# CM5_Adapter.net
KiCad netlist of a schematic drawn in Altium Designer
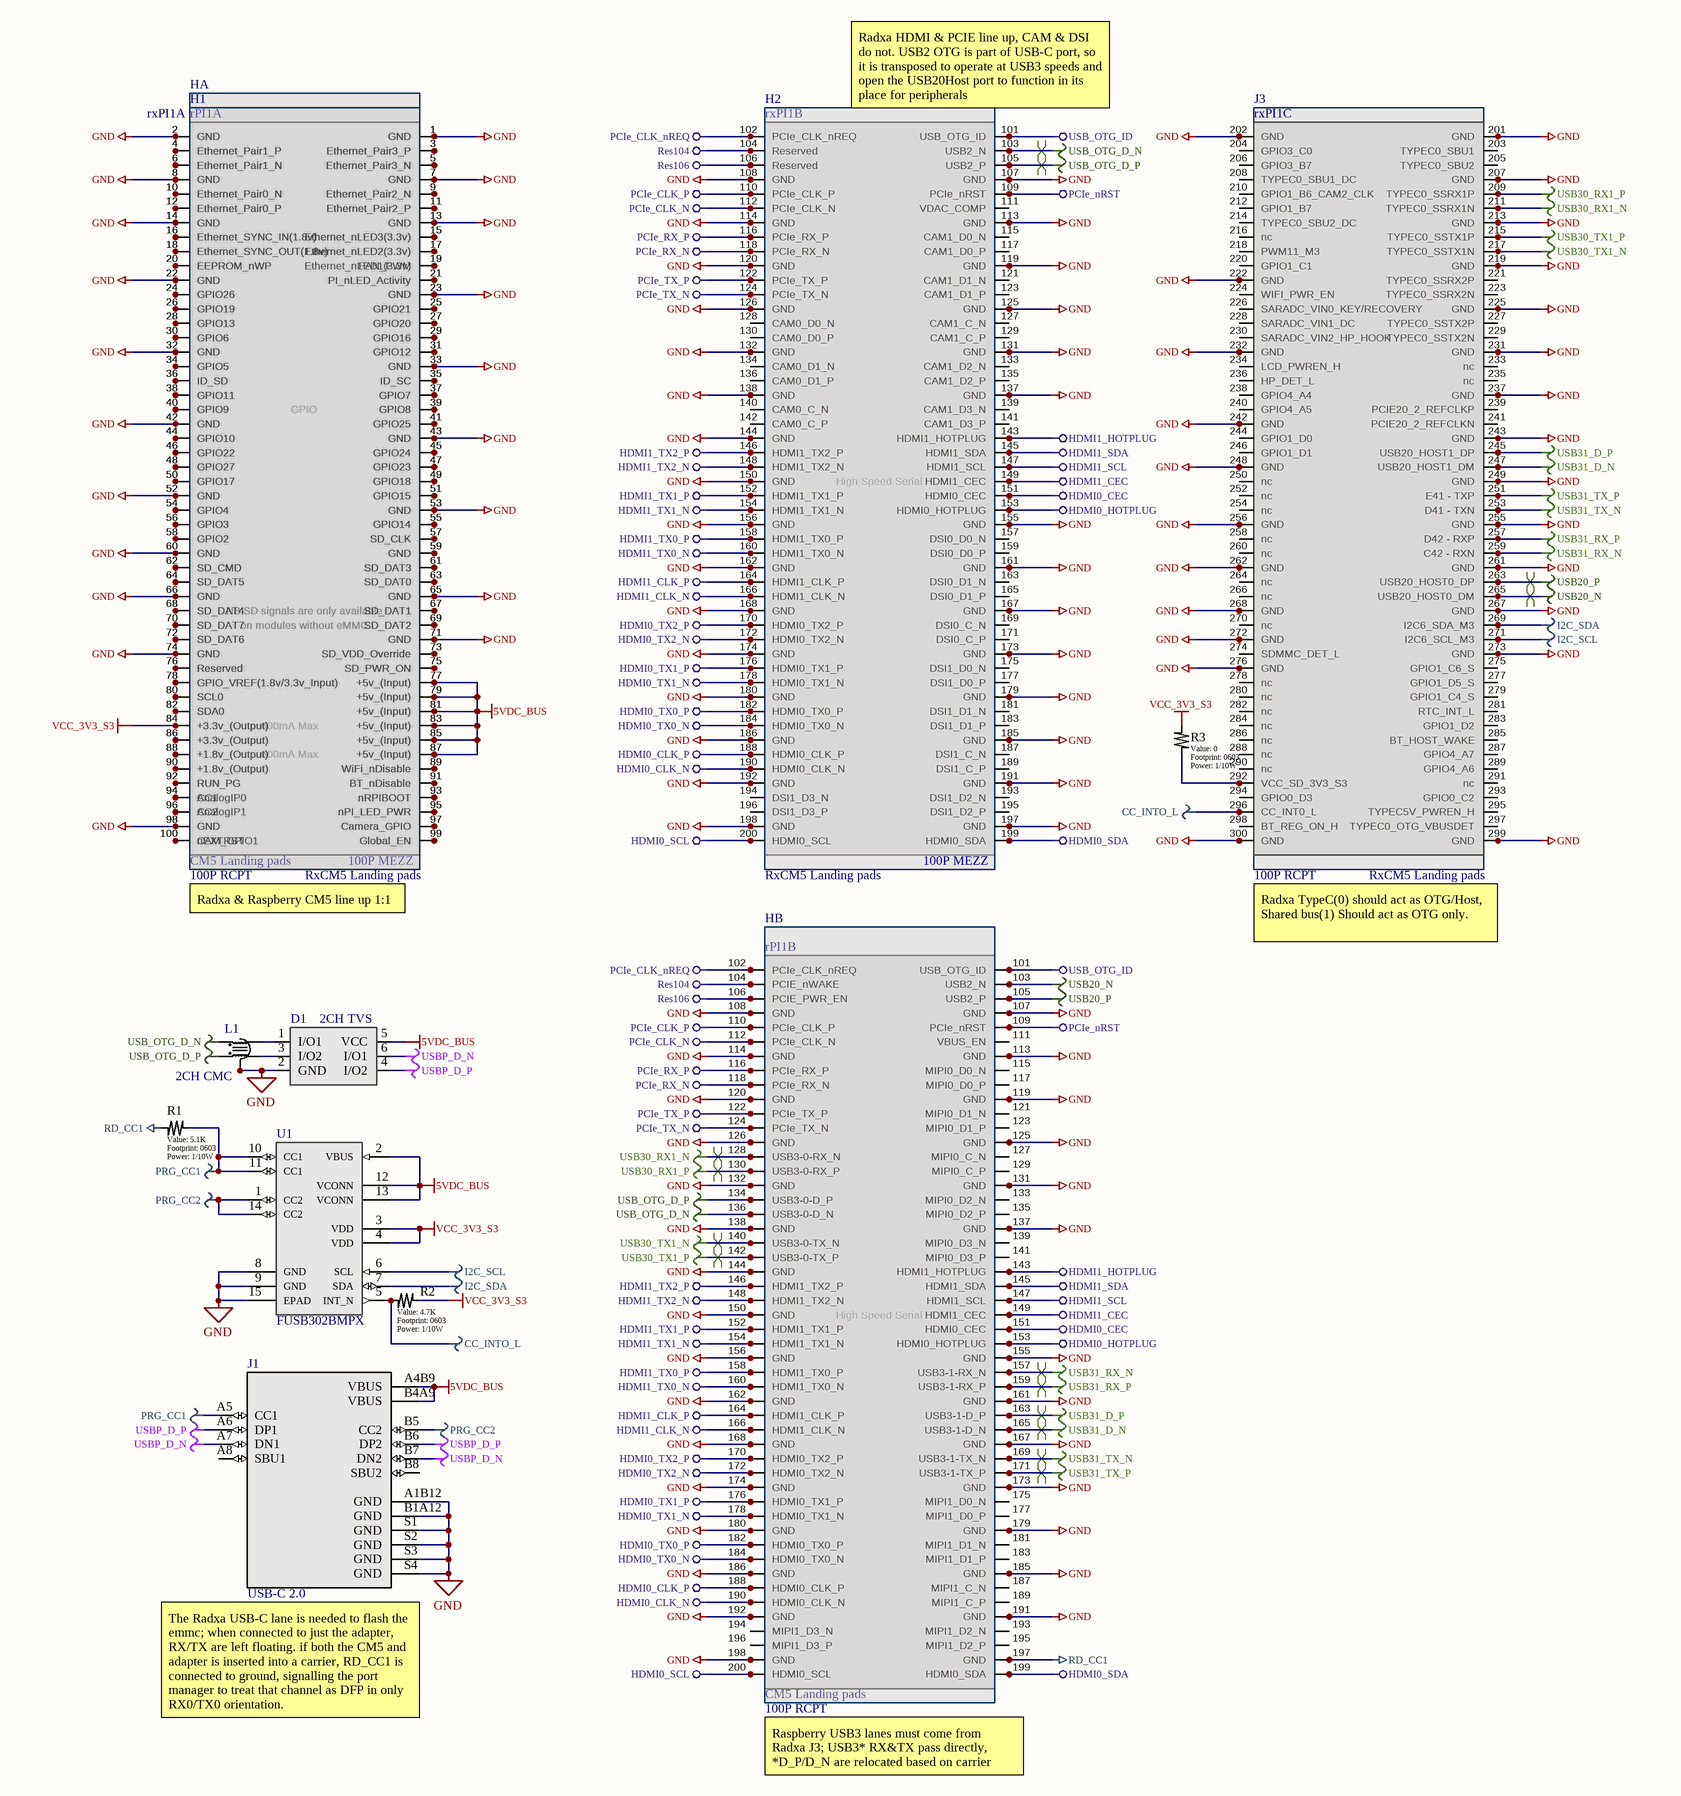
[diagram p0: CM5 Adapter.SchDoc]

(export (version "E")
  (design (tool "Eeschema 10.0.6"))
  (components
    (comp (ref "D1")
      (value "2CH TVS")
      (footprint "FP-SOT886-MFG")
      (description "TVS DIODE 5.5V 6XSON SOT886")
      (fields
        (field (name "OCTOPART") "https://octopart.com/prtr5v0u2f%2C115-nexperia-78741690")
        (field (name "MANUFACTURER") "Nexperia")
      )
      (libsource (lib "Diodes") (part "PRTR5V0U2F,115"))
    )
    (comp (ref "H1")
      (value "100P RCPT")
      (footprint "DF40C-100DS-0.4V(51)")
      (description "100 Position Connector Receptacle, Center Strip Contacts Surface Mount Gold")
      (fields (field (name "MF") "Hirose") (field (name "MP") "DF40C-100DS-0.4V(51)"))
      (libsource (lib "") (part "DF40-100DS RCPT_1_1"))
    )
    (comp (ref "H2")
      (value "100P MEZZ")
      (footprint "DF40C-100DS-0.4V(51)")
      (description "100 Position Connector Receptacle, Center Strip Contacts Surface Mount Gold")
      (fields (field (name "MF") "Hirose") (field (name "MP") "DF40C-100DS-0.4V(51)"))
      (libsource (lib "") (part "DF40-100DS RCPT_1_1"))
    )
    (comp (ref "HA")
      (value "100P MEZZ")
      (footprint "DF40C-100DP-0.4V(51)")
      (description "100 Position Connector Receptacle, Center Strip Contacts Surface Mount Gold")
      (fields (field (name "MF") "Hirose") (field (name "MP") "DF40C-100DS-0.4V(51)"))
      (libsource (lib "SOC_Carrier") (part "DF40-XX-100DS RCPT"))
    )
    (comp (ref "HB")
      (value "100P RCPT")
      (footprint "DF40C-100DP-0.4V(51)")
      (description "100 Position Connector Receptacle, Center Strip Contacts Surface Mount Gold")
      (fields (field (name "MF") "Hirose") (field (name "MP") "DF40C-100DS-0.4V(51)"))
      (libsource (lib "SOC_Carrier") (part "DF40-XX-100DS RCPT"))
    )
    (comp (ref "J1")
      (value "USB-C 2.0")
      (footprint "GT-USB-7010ASV")
      (libsource (lib "Connectors") (part "12402012E212A"))
    )
    (comp (ref "J3")
      (value "100P RCPT")
      (footprint "DF40C-100DS-0.4V(51)")
      (description "100 Position Connector Receptacle, Center Strip Contacts Surface Mount Gold")
      (fields (field (name "MF") "Hirose") (field (name "MP") "DF40C-100DS-0.4V(51)"))
      (libsource (lib "Connectors") (part "DF40-100DS RCPT_1"))
    )
    (comp (ref "L1")
      (value "2CH CMC")
      (footprint "SMD-6-2CH")
      (description "35Ω@100MHz -40℃~+85℃ 4Ω 5V 2 100mA SMD Common Mode Filters ROHS")
      (libsource (lib "Inductors") (part "ICMEF112P350MFR"))
    )
    (comp (ref "R1")
      (value "5.1K")
      (footprint "0603")
      (fields
        (field (name "TOLERANCE") "1%")
        (field (name "POWER") "1/10W")
        (field (name "Comment") "Generic Resistor")
      )
      (libsource (lib "Resistors") (part "Generic Resistor"))
    )
    (comp (ref "R2")
      (value "4.7K")
      (footprint "0603")
      (fields
        (field (name "TOLERANCE") "1%")
        (field (name "POWER") "1/10W")
        (field (name "Comment") "Generic Resistor")
      )
      (libsource (lib "Resistors") (part "Generic Resistor"))
    )
    (comp (ref "R3")
      (value "0")
      (footprint "0603")
      (fields
        (field (name "TOLERANCE") "1%")
        (field (name "POWER") "1/10W")
        (field (name "Comment") "Generic Resistor")
      )
      (libsource (lib "Resistors") (part "Generic Resistor"))
    )
    (comp (ref "rPI1")
      (value "CM5 Landing pads")
      (footprint "rP-200P-CM-REP (top)")
      (libsource (lib "SOC_Carrier") (part "RP-CM5-Rep"))
    )
    (comp (ref "rxPI1")
      (value "RxCM5 Landing pads")
      (footprint "RX-300P-CM-FTPD")
      (libsource (lib "SOC_Carrier") (part "RX-CM5"))
    )
    (comp (ref "U1")
      (value "FUSB302BMPX")
      (footprint "MLP14_2P5X2P5_ONS-L")
      (description "IC USB TYPE C CTLR PROGR 14-MLP")
      (fields (field (name "COPYRIGHT") "Copyright (C) 2025 Ultra Librarian. All rights reserved."))
      (libsource (lib "Misc ICs") (part "FUSB302BMPX"))
    )
  )
  (nets
    (net (code "1") (name "5VDC_BUS") (class "Default")
      (node (ref "D1") (pin "5") (pinfunction "VCC_5") (pintype "power_in"))
      (node (ref "H1") (pin "77") (pinfunction "77_77") (pintype "passive"))
      (node (ref "H1") (pin "79") (pinfunction "79_79") (pintype "passive"))
      (node (ref "H1") (pin "81") (pinfunction "81_81") (pintype "passive"))
      (node (ref "H1") (pin "83") (pinfunction "83_83") (pintype "passive"))
      (node (ref "H1") (pin "85") (pinfunction "85_85") (pintype "passive"))
      (node (ref "H1") (pin "87") (pinfunction "87_87") (pintype "passive"))
      (node (ref "HA") (pin "78") (pinfunction "78_78") (pintype "passive"))
      (node (ref "HA") (pin "80") (pinfunction "80_80") (pintype "passive"))
      (node (ref "HA") (pin "82") (pinfunction "82_82") (pintype "passive"))
      (node (ref "HA") (pin "84") (pinfunction "84_84") (pintype "passive"))
      (node (ref "HA") (pin "86") (pinfunction "86_86") (pintype "passive"))
      (node (ref "HA") (pin "88") (pinfunction "88_88") (pintype "passive"))
      (node (ref "J1") (pin "A4B9") (pinfunction "VBUS_A4B9") (pintype "power_in"))
      (node (ref "J1") (pin "B4A9") (pinfunction "VBUS_B4A9") (pintype "power_in"))
      (node (ref "U1") (pin "12") (pinfunction "VCONN_12") (pintype "power_in"))
      (node (ref "U1") (pin "13") (pinfunction "VCONN_13") (pintype "power_in"))
      (node (ref "U1") (pin "2") (pinfunction "VBUS_2") (pintype "input"))
      (node (ref "rPI1") (pin "77") (pinfunction "+5v_(Input)_77") (pintype "passive"))
      (node (ref "rPI1") (pin "79") (pinfunction "+5v_(Input)_79") (pintype "passive"))
      (node (ref "rPI1") (pin "81") (pinfunction "+5v_(Input)_81") (pintype "passive"))
      (node (ref "rPI1") (pin "83") (pinfunction "+5v_(Input)_83") (pintype "passive"))
      (node (ref "rPI1") (pin "85") (pinfunction "+5v_(Input)_85") (pintype "passive"))
      (node (ref "rPI1") (pin "87") (pinfunction "+5v_(Input)_87") (pintype "passive"))
      (node (ref "rxPI1") (pin "77") (pinfunction "+5v_(Input)_77") (pintype "passive"))
      (node (ref "rxPI1") (pin "79") (pinfunction "+5v_(Input)_79") (pintype "passive"))
      (node (ref "rxPI1") (pin "81") (pinfunction "+5v_(Input)_81") (pintype "passive"))
      (node (ref "rxPI1") (pin "83") (pinfunction "+5v_(Input)_83") (pintype "passive"))
      (node (ref "rxPI1") (pin "85") (pinfunction "+5v_(Input)_85") (pintype "passive"))
      (node (ref "rxPI1") (pin "87") (pinfunction "+5v_(Input)_87") (pintype "passive"))
    )
    (net (code "2") (name "CC_INTO_L") (class "Default")
      (node (ref "J3") (pin "95") (pinfunction "95_95") (pintype "passive"))
      (node (ref "R2") (pin "1") (pinfunction "1_1") (pintype "passive"))
      (node (ref "U1") (pin "5") (pinfunction "INT_N_5") (pintype "output"))
      (node (ref "rxPI1") (pin "296") (pinfunction "CC_INT0_L_296") (pintype "passive"))
    )
    (net (code "3") (name "GND") (class "Default")
      (node (ref "D1") (pin "2") (pinfunction "GND_2") (pintype "power_in"))
      (node (ref "H1") (pin "1") (pinfunction "1_1") (pintype "passive"))
      (node (ref "H1") (pin "13") (pinfunction "13_13") (pintype "passive"))
      (node (ref "H1") (pin "14") (pinfunction "14_14") (pintype "passive"))
      (node (ref "H1") (pin "2") (pinfunction "2_2") (pintype "passive"))
      (node (ref "H1") (pin "22") (pinfunction "22_22") (pintype "passive"))
      (node (ref "H1") (pin "23") (pinfunction "23_23") (pintype "passive"))
      (node (ref "H1") (pin "32") (pinfunction "32_32") (pintype "passive"))
      (node (ref "H1") (pin "33") (pinfunction "33_33") (pintype "passive"))
      (node (ref "H1") (pin "42") (pinfunction "42_42") (pintype "passive"))
      (node (ref "H1") (pin "43") (pinfunction "43_43") (pintype "passive"))
      (node (ref "H1") (pin "52") (pinfunction "52_52") (pintype "passive"))
      (node (ref "H1") (pin "53") (pinfunction "53_53") (pintype "passive"))
      (node (ref "H1") (pin "60") (pinfunction "60_60") (pintype "passive"))
      (node (ref "H1") (pin "65") (pinfunction "65_65") (pintype "passive"))
      (node (ref "H1") (pin "66") (pinfunction "66_66") (pintype "passive"))
      (node (ref "H1") (pin "7") (pinfunction "7_7") (pintype "passive"))
      (node (ref "H1") (pin "71") (pinfunction "71_71") (pintype "passive"))
      (node (ref "H1") (pin "74") (pinfunction "74_74") (pintype "passive"))
      (node (ref "H1") (pin "8") (pinfunction "8_8") (pintype "passive"))
      (node (ref "H1") (pin "98") (pinfunction "98_98") (pintype "passive"))
      (node (ref "H2") (pin "13") (pinfunction "13_13") (pintype "passive"))
      (node (ref "H2") (pin "14") (pinfunction "14_14") (pintype "passive"))
      (node (ref "H2") (pin "19") (pinfunction "19_19") (pintype "passive"))
      (node (ref "H2") (pin "20") (pinfunction "20_20") (pintype "passive"))
      (node (ref "H2") (pin "25") (pinfunction "25_25") (pintype "passive"))
      (node (ref "H2") (pin "26") (pinfunction "26_26") (pintype "passive"))
      (node (ref "H2") (pin "31") (pinfunction "31_31") (pintype "passive"))
      (node (ref "H2") (pin "32") (pinfunction "32_32") (pintype "passive"))
      (node (ref "H2") (pin "37") (pinfunction "37_37") (pintype "passive"))
      (node (ref "H2") (pin "38") (pinfunction "38_38") (pintype "passive"))
      (node (ref "H2") (pin "44") (pinfunction "44_44") (pintype "passive"))
      (node (ref "H2") (pin "50") (pinfunction "50_50") (pintype "passive"))
      (node (ref "H2") (pin "55") (pinfunction "55_55") (pintype "passive"))
      (node (ref "H2") (pin "56") (pinfunction "56_56") (pintype "passive"))
      (node (ref "H2") (pin "61") (pinfunction "61_61") (pintype "passive"))
      (node (ref "H2") (pin "62") (pinfunction "62_62") (pintype "passive"))
      (node (ref "H2") (pin "67") (pinfunction "67_67") (pintype "passive"))
      (node (ref "H2") (pin "68") (pinfunction "68_68") (pintype "passive"))
      (node (ref "H2") (pin "7") (pinfunction "7_7") (pintype "passive"))
      (node (ref "H2") (pin "73") (pinfunction "73_73") (pintype "passive"))
      (node (ref "H2") (pin "74") (pinfunction "74_74") (pintype "passive"))
      (node (ref "H2") (pin "79") (pinfunction "79_79") (pintype "passive"))
      (node (ref "H2") (pin "8") (pinfunction "8_8") (pintype "passive"))
      (node (ref "H2") (pin "80") (pinfunction "80_80") (pintype "passive"))
      (node (ref "H2") (pin "85") (pinfunction "85_85") (pintype "passive"))
      (node (ref "H2") (pin "86") (pinfunction "86_86") (pintype "passive"))
      (node (ref "H2") (pin "91") (pinfunction "91_91") (pintype "passive"))
      (node (ref "H2") (pin "92") (pinfunction "92_92") (pintype "passive"))
      (node (ref "H2") (pin "97") (pinfunction "97_97") (pintype "passive"))
      (node (ref "H2") (pin "98") (pinfunction "98_98") (pintype "passive"))
      (node (ref "HA") (pin "1") (pinfunction "1_1") (pintype "passive"))
      (node (ref "HA") (pin "13") (pinfunction "13_13") (pintype "passive"))
      (node (ref "HA") (pin "14") (pinfunction "14_14") (pintype "passive"))
      (node (ref "HA") (pin "2") (pinfunction "2_2") (pintype "passive"))
      (node (ref "HA") (pin "21") (pinfunction "21_21") (pintype "passive"))
      (node (ref "HA") (pin "24") (pinfunction "24_24") (pintype "passive"))
      (node (ref "HA") (pin "31") (pinfunction "31_31") (pintype "passive"))
      (node (ref "HA") (pin "34") (pinfunction "34_34") (pintype "passive"))
      (node (ref "HA") (pin "41") (pinfunction "41_41") (pintype "passive"))
      (node (ref "HA") (pin "44") (pinfunction "44_44") (pintype "passive"))
      (node (ref "HA") (pin "51") (pinfunction "51_51") (pintype "passive"))
      (node (ref "HA") (pin "54") (pinfunction "54_54") (pintype "passive"))
      (node (ref "HA") (pin "59") (pinfunction "59_59") (pintype "passive"))
      (node (ref "HA") (pin "65") (pinfunction "65_65") (pintype "passive"))
      (node (ref "HA") (pin "66") (pinfunction "66_66") (pintype "passive"))
      (node (ref "HA") (pin "7") (pinfunction "7_7") (pintype "passive"))
      (node (ref "HA") (pin "72") (pinfunction "72_72") (pintype "passive"))
      (node (ref "HA") (pin "73") (pinfunction "73_73") (pintype "passive"))
      (node (ref "HA") (pin "8") (pinfunction "8_8") (pintype "passive"))
      (node (ref "HA") (pin "97") (pinfunction "97_97") (pintype "passive"))
      (node (ref "HB") (pin "13") (pinfunction "13_13") (pintype "passive"))
      (node (ref "HB") (pin "14") (pinfunction "14_14") (pintype "passive"))
      (node (ref "HB") (pin "19") (pinfunction "19_19") (pintype "passive"))
      (node (ref "HB") (pin "20") (pinfunction "20_20") (pintype "passive"))
      (node (ref "HB") (pin "25") (pinfunction "25_25") (pintype "passive"))
      (node (ref "HB") (pin "26") (pinfunction "26_26") (pintype "passive"))
      (node (ref "HB") (pin "31") (pinfunction "31_31") (pintype "passive"))
      (node (ref "HB") (pin "32") (pinfunction "32_32") (pintype "passive"))
      (node (ref "HB") (pin "37") (pinfunction "37_37") (pintype "passive"))
      (node (ref "HB") (pin "38") (pinfunction "38_38") (pintype "passive"))
      (node (ref "HB") (pin "43") (pinfunction "43_43") (pintype "passive"))
      (node (ref "HB") (pin "49") (pinfunction "49_49") (pintype "passive"))
      (node (ref "HB") (pin "55") (pinfunction "55_55") (pintype "passive"))
      (node (ref "HB") (pin "56") (pinfunction "56_56") (pintype "passive"))
      (node (ref "HB") (pin "61") (pinfunction "61_61") (pintype "passive"))
      (node (ref "HB") (pin "62") (pinfunction "62_62") (pintype "passive"))
      (node (ref "HB") (pin "67") (pinfunction "67_67") (pintype "passive"))
      (node (ref "HB") (pin "68") (pinfunction "68_68") (pintype "passive"))
      (node (ref "HB") (pin "7") (pinfunction "7_7") (pintype "passive"))
      (node (ref "HB") (pin "73") (pinfunction "73_73") (pintype "passive"))
      (node (ref "HB") (pin "74") (pinfunction "74_74") (pintype "passive"))
      (node (ref "HB") (pin "79") (pinfunction "79_79") (pintype "passive"))
      (node (ref "HB") (pin "8") (pinfunction "8_8") (pintype "passive"))
      (node (ref "HB") (pin "80") (pinfunction "80_80") (pintype "passive"))
      (node (ref "HB") (pin "85") (pinfunction "85_85") (pintype "passive"))
      (node (ref "HB") (pin "86") (pinfunction "86_86") (pintype "passive"))
      (node (ref "HB") (pin "91") (pinfunction "91_91") (pintype "passive"))
      (node (ref "HB") (pin "92") (pinfunction "92_92") (pintype "passive"))
      (node (ref "HB") (pin "97") (pinfunction "97_97") (pintype "passive"))
      (node (ref "J1") (pin "A1B12") (pinfunction "GND_A1B12") (pintype "power_in"))
      (node (ref "J1") (pin "B1A12") (pinfunction "GND_B1A12") (pintype "power_in"))
      (node (ref "J1") (pin "S1") (pinfunction "GND_S1") (pintype "power_in"))
      (node (ref "J1") (pin "S2") (pinfunction "GND_S2") (pintype "power_in"))
      (node (ref "J1") (pin "S3") (pinfunction "GND_S3") (pintype "power_in"))
      (node (ref "J1") (pin "S4") (pinfunction "GND_S4") (pintype "power_in"))
      (node (ref "J3") (pin "1") (pinfunction "1_1") (pintype "passive"))
      (node (ref "J3") (pin "100") (pinfunction "100_100") (pintype "passive"))
      (node (ref "J3") (pin "14") (pinfunction "14_14") (pintype "passive"))
      (node (ref "J3") (pin "2") (pinfunction "2_2") (pintype "passive"))
      (node (ref "J3") (pin "20") (pinfunction "20_20") (pintype "passive"))
      (node (ref "J3") (pin "21") (pinfunction "21_21") (pintype "passive"))
      (node (ref "J3") (pin "26") (pinfunction "26_26") (pintype "passive"))
      (node (ref "J3") (pin "31") (pinfunction "31_31") (pintype "passive"))
      (node (ref "J3") (pin "32") (pinfunction "32_32") (pintype "passive"))
      (node (ref "J3") (pin "38") (pinfunction "38_38") (pintype "passive"))
      (node (ref "J3") (pin "41") (pinfunction "41_41") (pintype "passive"))
      (node (ref "J3") (pin "44") (pinfunction "44_44") (pintype "passive"))
      (node (ref "J3") (pin "47") (pinfunction "47_47") (pintype "passive"))
      (node (ref "J3") (pin "50") (pinfunction "50_50") (pintype "passive"))
      (node (ref "J3") (pin "55") (pinfunction "55_55") (pintype "passive"))
      (node (ref "J3") (pin "56") (pinfunction "56_56") (pintype "passive"))
      (node (ref "J3") (pin "61") (pinfunction "61_61") (pintype "passive"))
      (node (ref "J3") (pin "62") (pinfunction "62_62") (pintype "passive"))
      (node (ref "J3") (pin "67") (pinfunction "67_67") (pintype "passive"))
      (node (ref "J3") (pin "68") (pinfunction "68_68") (pintype "passive"))
      (node (ref "J3") (pin "71") (pinfunction "71_71") (pintype "passive"))
      (node (ref "J3") (pin "74") (pinfunction "74_74") (pintype "passive"))
      (node (ref "J3") (pin "75") (pinfunction "75_75") (pintype "passive"))
      (node (ref "J3") (pin "8") (pinfunction "8_8") (pintype "passive"))
      (node (ref "J3") (pin "99") (pinfunction "99_99") (pintype "passive"))
      (node (ref "L1") (pin "5") (pinfunction "5_5") (pintype "passive"))
      (node (ref "L1") (pin "6") (pinfunction "6_6") (pintype "passive"))
      (node (ref "U1") (pin "15") (pinfunction "EPAD_15") (pintype "passive"))
      (node (ref "U1") (pin "8") (pinfunction "GND_8") (pintype "power_in"))
      (node (ref "U1") (pin "9") (pinfunction "GND_9") (pintype "power_in"))
      (node (ref "rPI1") (pin "1") (pinfunction "GND_1") (pintype "passive"))
      (node (ref "rPI1") (pin "107") (pinfunction "GND_107") (pintype "passive"))
      (node (ref "rPI1") (pin "108") (pinfunction "GND_108") (pintype "passive"))
      (node (ref "rPI1") (pin "113") (pinfunction "GND_113") (pintype "passive"))
      (node (ref "rPI1") (pin "114") (pinfunction "GND_114") (pintype "passive"))
      (node (ref "rPI1") (pin "119") (pinfunction "GND_119") (pintype "passive"))
      (node (ref "rPI1") (pin "120") (pinfunction "GND_120") (pintype "passive"))
      (node (ref "rPI1") (pin "125") (pinfunction "GND_125") (pintype "passive"))
      (node (ref "rPI1") (pin "126") (pinfunction "GND_126") (pintype "passive"))
      (node (ref "rPI1") (pin "13") (pinfunction "GND_13") (pintype "passive"))
      (node (ref "rPI1") (pin "131") (pinfunction "GND_131") (pintype "passive"))
      (node (ref "rPI1") (pin "132") (pinfunction "GND_132") (pintype "passive"))
      (node (ref "rPI1") (pin "137") (pinfunction "GND_137") (pintype "passive"))
      (node (ref "rPI1") (pin "138") (pinfunction "GND_138") (pintype "passive"))
      (node (ref "rPI1") (pin "14") (pinfunction "GND_14") (pintype "passive"))
      (node (ref "rPI1") (pin "144") (pinfunction "GND_144") (pintype "passive"))
      (node (ref "rPI1") (pin "150") (pinfunction "GND_150") (pintype "passive"))
      (node (ref "rPI1") (pin "155") (pinfunction "GND_155") (pintype "passive"))
      (node (ref "rPI1") (pin "156") (pinfunction "GND_156") (pintype "passive"))
      (node (ref "rPI1") (pin "161") (pinfunction "GND_161") (pintype "passive"))
      (node (ref "rPI1") (pin "162") (pinfunction "GND_162") (pintype "passive"))
      (node (ref "rPI1") (pin "167") (pinfunction "GND_167") (pintype "passive"))
      (node (ref "rPI1") (pin "168") (pinfunction "GND_168") (pintype "passive"))
      (node (ref "rPI1") (pin "173") (pinfunction "GND_173") (pintype "passive"))
      (node (ref "rPI1") (pin "174") (pinfunction "GND_174") (pintype "passive"))
      (node (ref "rPI1") (pin "179") (pinfunction "GND_179") (pintype "passive"))
      (node (ref "rPI1") (pin "180") (pinfunction "GND_180") (pintype "passive"))
      (node (ref "rPI1") (pin "185") (pinfunction "GND_185") (pintype "passive"))
      (node (ref "rPI1") (pin "186") (pinfunction "GND_186") (pintype "passive"))
      (node (ref "rPI1") (pin "191") (pinfunction "GND_191") (pintype "passive"))
      (node (ref "rPI1") (pin "192") (pinfunction "GND_192") (pintype "passive"))
      (node (ref "rPI1") (pin "198") (pinfunction "GND_198") (pintype "passive"))
      (node (ref "rPI1") (pin "2") (pinfunction "GND_2") (pintype "passive"))
      (node (ref "rPI1") (pin "22") (pinfunction "GND_22") (pintype "passive"))
      (node (ref "rPI1") (pin "23") (pinfunction "GND_23") (pintype "passive"))
      (node (ref "rPI1") (pin "32") (pinfunction "GND_32") (pintype "passive"))
      (node (ref "rPI1") (pin "33") (pinfunction "GND_33") (pintype "passive"))
      (node (ref "rPI1") (pin "42") (pinfunction "GND_42") (pintype "passive"))
      (node (ref "rPI1") (pin "43") (pinfunction "GND_43") (pintype "passive"))
      (node (ref "rPI1") (pin "52") (pinfunction "GND_52") (pintype "passive"))
      (node (ref "rPI1") (pin "53") (pinfunction "GND_53") (pintype "passive"))
      (node (ref "rPI1") (pin "60") (pinfunction "GND_60") (pintype "passive"))
      (node (ref "rPI1") (pin "65") (pinfunction "GND_65") (pintype "passive"))
      (node (ref "rPI1") (pin "66") (pinfunction "GND_66") (pintype "passive"))
      (node (ref "rPI1") (pin "7") (pinfunction "GND_7") (pintype "passive"))
      (node (ref "rPI1") (pin "71") (pinfunction "GND_71") (pintype "passive"))
      (node (ref "rPI1") (pin "74") (pinfunction "GND_74") (pintype "passive"))
      (node (ref "rPI1") (pin "8") (pinfunction "GND_8") (pintype "passive"))
      (node (ref "rPI1") (pin "98") (pinfunction "GND_98") (pintype "passive"))
      (node (ref "rxPI1") (pin "1") (pinfunction "GND_1") (pintype "passive"))
      (node (ref "rxPI1") (pin "107") (pinfunction "GND_107") (pintype "passive"))
      (node (ref "rxPI1") (pin "108") (pinfunction "GND_108") (pintype "passive"))
      (node (ref "rxPI1") (pin "113") (pinfunction "GND_113") (pintype "passive"))
      (node (ref "rxPI1") (pin "114") (pinfunction "GND_114") (pintype "passive"))
      (node (ref "rxPI1") (pin "119") (pinfunction "GND_119") (pintype "passive"))
      (node (ref "rxPI1") (pin "120") (pinfunction "GND_120") (pintype "passive"))
      (node (ref "rxPI1") (pin "125") (pinfunction "GND_125") (pintype "passive"))
      (node (ref "rxPI1") (pin "126") (pinfunction "GND_126") (pintype "passive"))
      (node (ref "rxPI1") (pin "13") (pinfunction "GND_13") (pintype "passive"))
      (node (ref "rxPI1") (pin "131") (pinfunction "GND_131") (pintype "passive"))
      (node (ref "rxPI1") (pin "132") (pinfunction "GND_132") (pintype "passive"))
      (node (ref "rxPI1") (pin "137") (pinfunction "GND_137") (pintype "passive"))
      (node (ref "rxPI1") (pin "138") (pinfunction "GND_138") (pintype "passive"))
      (node (ref "rxPI1") (pin "14") (pinfunction "GND_14") (pintype "passive"))
      (node (ref "rxPI1") (pin "144") (pinfunction "GND_144") (pintype "passive"))
      (node (ref "rxPI1") (pin "150") (pinfunction "GND_150") (pintype "passive"))
      (node (ref "rxPI1") (pin "155") (pinfunction "GND_155") (pintype "passive"))
      (node (ref "rxPI1") (pin "156") (pinfunction "GND_156") (pintype "passive"))
      (node (ref "rxPI1") (pin "161") (pinfunction "GND_161") (pintype "passive"))
      (node (ref "rxPI1") (pin "162") (pinfunction "GND_162") (pintype "passive"))
      (node (ref "rxPI1") (pin "167") (pinfunction "GND_167") (pintype "passive"))
      (node (ref "rxPI1") (pin "168") (pinfunction "GND_168") (pintype "passive"))
      (node (ref "rxPI1") (pin "173") (pinfunction "GND_173") (pintype "passive"))
      (node (ref "rxPI1") (pin "174") (pinfunction "GND_174") (pintype "passive"))
      (node (ref "rxPI1") (pin "179") (pinfunction "GND_179") (pintype "passive"))
      (node (ref "rxPI1") (pin "180") (pinfunction "GND_180") (pintype "passive"))
      (node (ref "rxPI1") (pin "185") (pinfunction "GND_185") (pintype "passive"))
      (node (ref "rxPI1") (pin "186") (pinfunction "GND_186") (pintype "passive"))
      (node (ref "rxPI1") (pin "191") (pinfunction "GND_191") (pintype "passive"))
      (node (ref "rxPI1") (pin "192") (pinfunction "GND_192") (pintype "passive"))
      (node (ref "rxPI1") (pin "197") (pinfunction "GND_197") (pintype "passive"))
      (node (ref "rxPI1") (pin "198") (pinfunction "GND_198") (pintype "passive"))
      (node (ref "rxPI1") (pin "2") (pinfunction "GND_2") (pintype "passive"))
      (node (ref "rxPI1") (pin "201") (pinfunction "GND_201") (pintype "passive"))
      (node (ref "rxPI1") (pin "202") (pinfunction "GND_202") (pintype "passive"))
      (node (ref "rxPI1") (pin "207") (pinfunction "GND_207") (pintype "passive"))
      (node (ref "rxPI1") (pin "213") (pinfunction "GND_213") (pintype "passive"))
      (node (ref "rxPI1") (pin "219") (pinfunction "GND_219") (pintype "passive"))
      (node (ref "rxPI1") (pin "22") (pinfunction "GND_22") (pintype "passive"))
      (node (ref "rxPI1") (pin "222") (pinfunction "GND_222") (pintype "passive"))
      (node (ref "rxPI1") (pin "225") (pinfunction "GND_225") (pintype "passive"))
      (node (ref "rxPI1") (pin "23") (pinfunction "GND_23") (pintype "passive"))
      (node (ref "rxPI1") (pin "231") (pinfunction "GND_231") (pintype "passive"))
      (node (ref "rxPI1") (pin "232") (pinfunction "GND_232") (pintype "passive"))
      (node (ref "rxPI1") (pin "237") (pinfunction "GND_237") (pintype "passive"))
      (node (ref "rxPI1") (pin "242") (pinfunction "GND_242") (pintype "passive"))
      (node (ref "rxPI1") (pin "243") (pinfunction "GND_243") (pintype "passive"))
      (node (ref "rxPI1") (pin "248") (pinfunction "GND_248") (pintype "passive"))
      (node (ref "rxPI1") (pin "249") (pinfunction "GND_249") (pintype "passive"))
      (node (ref "rxPI1") (pin "255") (pinfunction "GND_255") (pintype "passive"))
      (node (ref "rxPI1") (pin "256") (pinfunction "GND_256") (pintype "passive"))
      (node (ref "rxPI1") (pin "261") (pinfunction "GND_261") (pintype "passive"))
      (node (ref "rxPI1") (pin "262") (pinfunction "GND_262") (pintype "passive"))
      (node (ref "rxPI1") (pin "267") (pinfunction "GND_267") (pintype "passive"))
      (node (ref "rxPI1") (pin "268") (pinfunction "GND_268") (pintype "passive"))
      (node (ref "rxPI1") (pin "272") (pinfunction "GND_272") (pintype "passive"))
      (node (ref "rxPI1") (pin "273") (pinfunction "GND_273") (pintype "passive"))
      (node (ref "rxPI1") (pin "276") (pinfunction "GND_276") (pintype "passive"))
      (node (ref "rxPI1") (pin "299") (pinfunction "GND_299") (pintype "passive"))
      (node (ref "rxPI1") (pin "300") (pinfunction "GND_300") (pintype "passive"))
      (node (ref "rxPI1") (pin "32") (pinfunction "GND_32") (pintype "passive"))
      (node (ref "rxPI1") (pin "33") (pinfunction "GND_33") (pintype "passive"))
      (node (ref "rxPI1") (pin "42") (pinfunction "GND_42") (pintype "passive"))
      (node (ref "rxPI1") (pin "43") (pinfunction "GND_43") (pintype "passive"))
      (node (ref "rxPI1") (pin "52") (pinfunction "GND_52") (pintype "passive"))
      (node (ref "rxPI1") (pin "53") (pinfunction "GND_53") (pintype "passive"))
      (node (ref "rxPI1") (pin "60") (pinfunction "GND_60") (pintype "passive"))
      (node (ref "rxPI1") (pin "65") (pinfunction "GND_65") (pintype "passive"))
      (node (ref "rxPI1") (pin "66") (pinfunction "GND_66") (pintype "passive"))
      (node (ref "rxPI1") (pin "7") (pinfunction "GND_7") (pintype "passive"))
      (node (ref "rxPI1") (pin "71") (pinfunction "GND_71") (pintype "passive"))
      (node (ref "rxPI1") (pin "74") (pinfunction "GND_74") (pintype "passive"))
      (node (ref "rxPI1") (pin "8") (pinfunction "GND_8") (pintype "passive"))
      (node (ref "rxPI1") (pin "98") (pinfunction "GND_98") (pintype "passive"))
    )
    (net (code "4") (name "HDMI0_CEC") (class "Default")
      (node (ref "H2") (pin "51") (pinfunction "51_51") (pintype "passive"))
      (node (ref "HB") (pin "52") (pinfunction "52_52") (pintype "passive"))
      (node (ref "rPI1") (pin "151") (pinfunction "HDMI0_CEC_151") (pintype "passive"))
      (node (ref "rxPI1") (pin "151") (pinfunction "HDMI0_CEC_151") (pintype "passive"))
    )
    (net (code "5") (name "HDMI0_CLK_N") (class "Default")
      (node (ref "H2") (pin "90") (pinfunction "90_90") (pintype "passive"))
      (node (ref "HB") (pin "89") (pinfunction "89_89") (pintype "passive"))
      (node (ref "rPI1") (pin "190") (pinfunction "HDMI0_CLK_N_190") (pintype "passive"))
      (node (ref "rxPI1") (pin "190") (pinfunction "HDMI0_CLK_N_190") (pintype "passive"))
    )
    (net (code "6") (name "HDMI0_CLK_P") (class "Default")
      (node (ref "H2") (pin "88") (pinfunction "88_88") (pintype "passive"))
      (node (ref "HB") (pin "87") (pinfunction "87_87") (pintype "passive"))
      (node (ref "rPI1") (pin "188") (pinfunction "HDMI0_CLK_P_188") (pintype "passive"))
      (node (ref "rxPI1") (pin "188") (pinfunction "HDMI0_CLK_P_188") (pintype "passive"))
    )
    (net (code "7") (name "HDMI0_HOTPLUG") (class "Default")
      (node (ref "H2") (pin "53") (pinfunction "53_53") (pintype "passive"))
      (node (ref "HB") (pin "54") (pinfunction "54_54") (pintype "passive"))
      (node (ref "rPI1") (pin "153") (pinfunction "HDMI0_HOTPLUG_153") (pintype "passive"))
      (node (ref "rxPI1") (pin "153") (pinfunction "HDMI0_HOTPLUG_153") (pintype "passive"))
    )
    (net (code "8") (name "HDMI0_SCL") (class "Default")
      (node (ref "H2") (pin "100") (pinfunction "100_100") (pintype "passive"))
      (node (ref "HB") (pin "99") (pinfunction "99_99") (pintype "passive"))
      (node (ref "rPI1") (pin "200") (pinfunction "HDMI0_SCL_200") (pintype "passive"))
      (node (ref "rxPI1") (pin "200") (pinfunction "HDMI0_SCL_200") (pintype "passive"))
    )
    (net (code "9") (name "HDMI0_SDA") (class "Default")
      (node (ref "H2") (pin "99") (pinfunction "99_99") (pintype "passive"))
      (node (ref "HB") (pin "100") (pinfunction "100_100") (pintype "passive"))
      (node (ref "rPI1") (pin "199") (pinfunction "HDMI0_SDA_199") (pintype "passive"))
      (node (ref "rxPI1") (pin "199") (pinfunction "HDMI0_SDA_199") (pintype "passive"))
    )
    (net (code "10") (name "HDMI0_TX0_N") (class "Default")
      (node (ref "H2") (pin "84") (pinfunction "84_84") (pintype "passive"))
      (node (ref "HB") (pin "83") (pinfunction "83_83") (pintype "passive"))
      (node (ref "rPI1") (pin "184") (pinfunction "HDMI0_TX0_N_184") (pintype "passive"))
      (node (ref "rxPI1") (pin "184") (pinfunction "HDMI0_TX0_N_184") (pintype "passive"))
    )
    (net (code "11") (name "HDMI0_TX0_P") (class "Default")
      (node (ref "H2") (pin "82") (pinfunction "82_82") (pintype "passive"))
      (node (ref "HB") (pin "81") (pinfunction "81_81") (pintype "passive"))
      (node (ref "rPI1") (pin "182") (pinfunction "HDMI0_TX0_P_182") (pintype "passive"))
      (node (ref "rxPI1") (pin "182") (pinfunction "HDMI0_TX0_P_182") (pintype "passive"))
    )
    (net (code "12") (name "HDMI0_TX1_N") (class "Default")
      (node (ref "H2") (pin "78") (pinfunction "78_78") (pintype "passive"))
      (node (ref "HB") (pin "77") (pinfunction "77_77") (pintype "passive"))
      (node (ref "rPI1") (pin "178") (pinfunction "HDMI0_TX1_N_178") (pintype "passive"))
      (node (ref "rxPI1") (pin "178") (pinfunction "HDMI0_TX1_N_178") (pintype "passive"))
    )
    (net (code "13") (name "HDMI0_TX1_P") (class "Default")
      (node (ref "H2") (pin "76") (pinfunction "76_76") (pintype "passive"))
      (node (ref "HB") (pin "75") (pinfunction "75_75") (pintype "passive"))
      (node (ref "rPI1") (pin "176") (pinfunction "HDMI0_TX1_P_176") (pintype "passive"))
      (node (ref "rxPI1") (pin "176") (pinfunction "HDMI0_TX1_P_176") (pintype "passive"))
    )
    (net (code "14") (name "HDMI0_TX2_N") (class "Default")
      (node (ref "H2") (pin "72") (pinfunction "72_72") (pintype "passive"))
      (node (ref "HB") (pin "71") (pinfunction "71_71") (pintype "passive"))
      (node (ref "rPI1") (pin "172") (pinfunction "HDMI0_TX2_N_172") (pintype "passive"))
      (node (ref "rxPI1") (pin "172") (pinfunction "HDMI0_TX2_N_172") (pintype "passive"))
    )
    (net (code "15") (name "HDMI0_TX2_P") (class "Default")
      (node (ref "H2") (pin "70") (pinfunction "70_70") (pintype "passive"))
      (node (ref "HB") (pin "69") (pinfunction "69_69") (pintype "passive"))
      (node (ref "rPI1") (pin "170") (pinfunction "HDMI0_TX2_P_170") (pintype "passive"))
      (node (ref "rxPI1") (pin "170") (pinfunction "HDMI0_TX2_P_170") (pintype "passive"))
    )
    (net (code "16") (name "HDMI1_CEC") (class "Default")
      (node (ref "H2") (pin "49") (pinfunction "49_49") (pintype "passive"))
      (node (ref "HB") (pin "50") (pinfunction "50_50") (pintype "passive"))
      (node (ref "rPI1") (pin "149") (pinfunction "HDMI1_CEC_149") (pintype "passive"))
      (node (ref "rxPI1") (pin "149") (pinfunction "HDMI1_CEC_149") (pintype "passive"))
    )
    (net (code "17") (name "HDMI1_CLK_N") (class "Default")
      (node (ref "H2") (pin "66") (pinfunction "66_66") (pintype "passive"))
      (node (ref "HB") (pin "65") (pinfunction "65_65") (pintype "passive"))
      (node (ref "rPI1") (pin "166") (pinfunction "HDMI1_CLK_N_166") (pintype "passive"))
      (node (ref "rxPI1") (pin "166") (pinfunction "HDMI1_CLK_N_166") (pintype "passive"))
    )
    (net (code "18") (name "HDMI1_CLK_P") (class "Default")
      (node (ref "H2") (pin "64") (pinfunction "64_64") (pintype "passive"))
      (node (ref "HB") (pin "63") (pinfunction "63_63") (pintype "passive"))
      (node (ref "rPI1") (pin "164") (pinfunction "HDMI1_CLK_P_164") (pintype "passive"))
      (node (ref "rxPI1") (pin "164") (pinfunction "HDMI1_CLK_P_164") (pintype "passive"))
    )
    (net (code "19") (name "HDMI1_HOTPLUG") (class "Default")
      (node (ref "H2") (pin "43") (pinfunction "43_43") (pintype "passive"))
      (node (ref "HB") (pin "44") (pinfunction "44_44") (pintype "passive"))
      (node (ref "rPI1") (pin "143") (pinfunction "HDMI1_HOTPLUG_143") (pintype "passive"))
      (node (ref "rxPI1") (pin "143") (pinfunction "HDMI1_HOTPLUG_143") (pintype "passive"))
    )
    (net (code "20") (name "HDMI1_SCL") (class "Default")
      (node (ref "H2") (pin "47") (pinfunction "47_47") (pintype "passive"))
      (node (ref "HB") (pin "48") (pinfunction "48_48") (pintype "passive"))
      (node (ref "rPI1") (pin "147") (pinfunction "HDMI1_SCL_147") (pintype "passive"))
      (node (ref "rxPI1") (pin "147") (pinfunction "HDMI1_SCL_147") (pintype "passive"))
    )
    (net (code "21") (name "HDMI1_SDA") (class "Default")
      (node (ref "H2") (pin "45") (pinfunction "45_45") (pintype "passive"))
      (node (ref "HB") (pin "46") (pinfunction "46_46") (pintype "passive"))
      (node (ref "rPI1") (pin "145") (pinfunction "HDMI1_SDA_145") (pintype "passive"))
      (node (ref "rxPI1") (pin "145") (pinfunction "HDMI1_SDA_145") (pintype "passive"))
    )
    (net (code "22") (name "HDMI1_TX0_N") (class "Default")
      (node (ref "H2") (pin "60") (pinfunction "60_60") (pintype "passive"))
      (node (ref "HB") (pin "59") (pinfunction "59_59") (pintype "passive"))
      (node (ref "rPI1") (pin "160") (pinfunction "HDMI1_TX0_N_160") (pintype "passive"))
      (node (ref "rxPI1") (pin "160") (pinfunction "HDMI1_TX0_N_160") (pintype "passive"))
    )
    (net (code "23") (name "HDMI1_TX0_P") (class "Default")
      (node (ref "H2") (pin "58") (pinfunction "58_58") (pintype "passive"))
      (node (ref "HB") (pin "57") (pinfunction "57_57") (pintype "passive"))
      (node (ref "rPI1") (pin "158") (pinfunction "HDMI1_TX0_P_158") (pintype "passive"))
      (node (ref "rxPI1") (pin "158") (pinfunction "HDMI1_TX0_P_158") (pintype "passive"))
    )
    (net (code "24") (name "HDMI1_TX1_N") (class "Default")
      (node (ref "H2") (pin "54") (pinfunction "54_54") (pintype "passive"))
      (node (ref "HB") (pin "53") (pinfunction "53_53") (pintype "passive"))
      (node (ref "rPI1") (pin "154") (pinfunction "HDMI1_TX1_N_154") (pintype "passive"))
      (node (ref "rxPI1") (pin "154") (pinfunction "HDMI1_TX1_N_154") (pintype "passive"))
    )
    (net (code "25") (name "HDMI1_TX1_P") (class "Default")
      (node (ref "H2") (pin "52") (pinfunction "52_52") (pintype "passive"))
      (node (ref "HB") (pin "51") (pinfunction "51_51") (pintype "passive"))
      (node (ref "rPI1") (pin "152") (pinfunction "HDMI1_TX1_P_152") (pintype "passive"))
      (node (ref "rxPI1") (pin "152") (pinfunction "HDMI1_TX1_P_152") (pintype "passive"))
    )
    (net (code "26") (name "HDMI1_TX2_N") (class "Default")
      (node (ref "H2") (pin "48") (pinfunction "48_48") (pintype "passive"))
      (node (ref "HB") (pin "47") (pinfunction "47_47") (pintype "passive"))
      (node (ref "rPI1") (pin "148") (pinfunction "HDMI1_TX2_N_148") (pintype "passive"))
      (node (ref "rxPI1") (pin "148") (pinfunction "HDMI1_TX2_N_148") (pintype "passive"))
    )
    (net (code "27") (name "HDMI1_TX2_P") (class "Default")
      (node (ref "H2") (pin "46") (pinfunction "46_46") (pintype "passive"))
      (node (ref "HB") (pin "45") (pinfunction "45_45") (pintype "passive"))
      (node (ref "rPI1") (pin "146") (pinfunction "HDMI1_TX2_P_146") (pintype "passive"))
      (node (ref "rxPI1") (pin "146") (pinfunction "HDMI1_TX2_P_146") (pintype "passive"))
    )
    (net (code "28") (name "I2C_SCL") (class "Default")
      (node (ref "J3") (pin "72") (pinfunction "72_72") (pintype "passive"))
      (node (ref "U1") (pin "6") (pinfunction "SCL_6") (pintype "input"))
      (node (ref "rxPI1") (pin "271") (pinfunction "I2C6_SCL_M3_271") (pintype "passive"))
    )
    (net (code "29") (name "I2C_SDA") (class "Default")
      (node (ref "J3") (pin "70") (pinfunction "70_70") (pintype "passive"))
      (node (ref "U1") (pin "7") (pinfunction "SDA_7") (pintype "bidirectional"))
      (node (ref "rxPI1") (pin "269") (pinfunction "I2C6_SDA_M3_269") (pintype "passive"))
    )
    (net (code "30") (name "Net-(D1-I{slash}O1-Pad1)") (class "Default")
      (node (ref "D1") (pin "1") (pinfunction "I/O1_1") (pintype "bidirectional"))
      (node (ref "L1") (pin "4") (pinfunction "4_4") (pintype "passive"))
    )
    (net (code "31") (name "Net-(D1-I{slash}O2-Pad3)") (class "Default")
      (node (ref "D1") (pin "3") (pinfunction "I/O2_3") (pintype "bidirectional"))
      (node (ref "L1") (pin "3") (pinfunction "3_3") (pintype "passive"))
    )
    (net (code "32") (name "Net-(H1-Pad59)") (class "Default")
      (node (ref "H1") (pin "59") (pinfunction "59_59") (pintype "passive"))
      (node (ref "HA") (pin "60") (pinfunction "60_60") (pintype "passive"))
      (node (ref "rPI1") (pin "59") (pinfunction "GND_59") (pintype "passive"))
      (node (ref "rxPI1") (pin "59") (pinfunction "GND_59") (pintype "passive"))
    )
    (net (code "33") (name "Net-(H1-Pad86)") (class "Default")
      (node (ref "H1") (pin "86") (pinfunction "86_86") (pintype "passive"))
      (node (ref "HA") (pin "85") (pinfunction "85_85") (pintype "passive"))
      (node (ref "rPI1") (pin "86") (pinfunction "+3.3v_(Output)_86") (pintype "passive"))
      (node (ref "rxPI1") (pin "86") (pinfunction "+3.3v_(Output)_86") (pintype "passive"))
    )
    (net (code "34") (name "Net-(H1-Pad88)") (class "Default")
      (node (ref "H1") (pin "88") (pinfunction "88_88") (pintype "passive"))
      (node (ref "HA") (pin "87") (pinfunction "87_87") (pintype "passive"))
      (node (ref "rPI1") (pin "88") (pinfunction "+1.8v_(Output)_88") (pintype "passive"))
      (node (ref "rxPI1") (pin "88") (pinfunction "+1.8v_(Output)_88") (pintype "passive"))
    )
    (net (code "35") (name "Net-(H1-Pad90)") (class "Default")
      (node (ref "H1") (pin "90") (pinfunction "90_90") (pintype "passive"))
      (node (ref "HA") (pin "89") (pinfunction "89_89") (pintype "passive"))
      (node (ref "rPI1") (pin "90") (pinfunction "+1.8v_(Output)_90") (pintype "passive"))
      (node (ref "rxPI1") (pin "90") (pinfunction "+1.8v_(Output)_90") (pintype "passive"))
    )
    (net (code "36") (name "Net-(J3-Pad15)") (class "Default")
      (node (ref "J3") (pin "15") (pinfunction "15_15") (pintype "passive"))
      (node (ref "rxPI1") (pin "216") (pinfunction "nc_216") (pintype "passive"))
    )
    (net (code "37") (name "Net-(J3-Pad34)") (class "Default")
      (node (ref "J3") (pin "34") (pinfunction "34_34") (pintype "passive"))
      (node (ref "rxPI1") (pin "233") (pinfunction "nc_233") (pintype "passive"))
    )
    (net (code "38") (name "Net-(J3-Pad36)") (class "Default")
      (node (ref "J3") (pin "36") (pinfunction "36_36") (pintype "passive"))
      (node (ref "rxPI1") (pin "235") (pinfunction "nc_235") (pintype "passive"))
    )
    (net (code "39") (name "Net-(J3-Pad49)") (class "Default")
      (node (ref "J3") (pin "49") (pinfunction "49_49") (pintype "passive"))
      (node (ref "rxPI1") (pin "250") (pinfunction "nc_250") (pintype "passive"))
    )
    (net (code "40") (name "Net-(J3-Pad51)") (class "Default")
      (node (ref "J3") (pin "51") (pinfunction "51_51") (pintype "passive"))
      (node (ref "rxPI1") (pin "252") (pinfunction "nc_252") (pintype "passive"))
    )
    (net (code "41") (name "Net-(J3-Pad53)") (class "Default")
      (node (ref "J3") (pin "53") (pinfunction "53_53") (pintype "passive"))
      (node (ref "rxPI1") (pin "254") (pinfunction "nc_254") (pintype "passive"))
    )
    (net (code "42") (name "Net-(J3-Pad57)") (class "Default")
      (node (ref "J3") (pin "57") (pinfunction "57_57") (pintype "passive"))
      (node (ref "rxPI1") (pin "258") (pinfunction "nc_258") (pintype "passive"))
    )
    (net (code "43") (name "Net-(J3-Pad59)") (class "Default")
      (node (ref "J3") (pin "59") (pinfunction "59_59") (pintype "passive"))
      (node (ref "rxPI1") (pin "260") (pinfunction "nc_260") (pintype "passive"))
    )
    (net (code "44") (name "Net-(J3-Pad63)") (class "Default")
      (node (ref "J3") (pin "63") (pinfunction "63_63") (pintype "passive"))
      (node (ref "rxPI1") (pin "264") (pinfunction "nc_264") (pintype "passive"))
    )
    (net (code "45") (name "Net-(J3-Pad65)") (class "Default")
      (node (ref "J3") (pin "65") (pinfunction "65_65") (pintype "passive"))
      (node (ref "rxPI1") (pin "266") (pinfunction "nc_266") (pintype "passive"))
    )
    (net (code "46") (name "Net-(J3-Pad69)") (class "Default")
      (node (ref "J3") (pin "69") (pinfunction "69_69") (pintype "passive"))
      (node (ref "rxPI1") (pin "270") (pinfunction "nc_270") (pintype "passive"))
    )
    (net (code "47") (name "Net-(J3-Pad77)") (class "Default")
      (node (ref "J3") (pin "77") (pinfunction "77_77") (pintype "passive"))
      (node (ref "rxPI1") (pin "278") (pinfunction "nc_278") (pintype "passive"))
    )
    (net (code "48") (name "Net-(J3-Pad79)") (class "Default")
      (node (ref "J3") (pin "79") (pinfunction "79_79") (pintype "passive"))
      (node (ref "rxPI1") (pin "280") (pinfunction "nc_280") (pintype "passive"))
    )
    (net (code "49") (name "Net-(J3-Pad81)") (class "Default")
      (node (ref "J3") (pin "81") (pinfunction "81_81") (pintype "passive"))
      (node (ref "rxPI1") (pin "282") (pinfunction "nc_282") (pintype "passive"))
    )
    (net (code "50") (name "Net-(J3-Pad83)") (class "Default")
      (node (ref "J3") (pin "83") (pinfunction "83_83") (pintype "passive"))
      (node (ref "rxPI1") (pin "284") (pinfunction "nc_284") (pintype "passive"))
    )
    (net (code "51") (name "Net-(J3-Pad85)") (class "Default")
      (node (ref "J3") (pin "85") (pinfunction "85_85") (pintype "passive"))
      (node (ref "rxPI1") (pin "286") (pinfunction "nc_286") (pintype "passive"))
    )
    (net (code "52") (name "Net-(J3-Pad87)") (class "Default")
      (node (ref "J3") (pin "87") (pinfunction "87_87") (pintype "passive"))
      (node (ref "rxPI1") (pin "288") (pinfunction "nc_288") (pintype "passive"))
    )
    (net (code "53") (name "Net-(J3-Pad89)") (class "Default")
      (node (ref "J3") (pin "89") (pinfunction "89_89") (pintype "passive"))
      (node (ref "rxPI1") (pin "290") (pinfunction "nc_290") (pintype "passive"))
    )
    (net (code "54") (name "Net-(J3-Pad92)") (class "Default")
      (node (ref "J3") (pin "92") (pinfunction "92_92") (pintype "passive"))
      (node (ref "rxPI1") (pin "291") (pinfunction "nc_291") (pintype "passive"))
    )
    (net (code "55") (name "Net-(rPI1A-BT_nDisable)") (class "Default")
      (node (ref "H1") (pin "91") (pinfunction "91_91") (pintype "passive"))
      (node (ref "HA") (pin "92") (pinfunction "92_92") (pintype "passive"))
      (node (ref "rPI1") (pin "91") (pinfunction "BT_nDisable_91") (pintype "passive"))
      (node (ref "rxPI1") (pin "91") (pinfunction "BT_nDisable_91") (pintype "passive"))
    )
    (net (code "56") (name "Net-(rPI1A-CAM_GPIO1)") (class "Default")
      (node (ref "H1") (pin "100") (pinfunction "100_100") (pintype "passive"))
      (node (ref "HA") (pin "99") (pinfunction "99_99") (pintype "passive"))
      (node (ref "rPI1") (pin "100") (pinfunction "CAM_GPIO1_100") (pintype "passive"))
      (node (ref "rxPI1") (pin "100") (pinfunction "nEXTRST_100") (pintype "passive"))
    )
    (net (code "57") (name "Net-(rPI1A-CC1)") (class "Default")
      (node (ref "H1") (pin "94") (pinfunction "94_94") (pintype "passive"))
      (node (ref "HA") (pin "93") (pinfunction "93_93") (pintype "passive"))
      (node (ref "rPI1") (pin "94") (pinfunction "CC1_94") (pintype "passive"))
      (node (ref "rxPI1") (pin "94") (pinfunction "AnalogIP0_94") (pintype "passive"))
    )
    (net (code "58") (name "Net-(rPI1A-CC2)") (class "Default")
      (node (ref "H1") (pin "96") (pinfunction "96_96") (pintype "passive"))
      (node (ref "HA") (pin "95") (pinfunction "95_95") (pintype "passive"))
      (node (ref "rPI1") (pin "96") (pinfunction "CC2_96") (pintype "passive"))
      (node (ref "rxPI1") (pin "96") (pinfunction "AnalogIP1_96") (pintype "passive"))
    )
    (net (code "59") (name "Net-(rPI1A-Camera_GPIO)") (class "Default")
      (node (ref "H1") (pin "97") (pinfunction "97_97") (pintype "passive"))
      (node (ref "HA") (pin "98") (pinfunction "98_98") (pintype "passive"))
      (node (ref "rPI1") (pin "97") (pinfunction "Camera_GPIO_97") (pintype "passive"))
      (node (ref "rxPI1") (pin "97") (pinfunction "Camera_GPIO_97") (pintype "passive"))
    )
    (net (code "60") (name "Net-(rPI1A-EEPROM_nWP)") (class "Default")
      (node (ref "H1") (pin "20") (pinfunction "20_20") (pintype "passive"))
      (node (ref "HA") (pin "19") (pinfunction "19_19") (pintype "passive"))
      (node (ref "rPI1") (pin "20") (pinfunction "EEPROM_nWP_20") (pintype "passive"))
      (node (ref "rxPI1") (pin "20") (pinfunction "EEPROM_nWP_20") (pintype "passive"))
    )
    (net (code "61") (name "Net-(rPI1A-Ethernet_Pair0_N)") (class "Default")
      (node (ref "H1") (pin "10") (pinfunction "10_10") (pintype "passive"))
      (node (ref "HA") (pin "9") (pinfunction "9_9") (pintype "passive"))
      (node (ref "rPI1") (pin "10") (pinfunction "Ethernet_Pair0_N_10") (pintype "passive"))
      (node (ref "rxPI1") (pin "10") (pinfunction "Ethernet_Pair0_N_10") (pintype "passive"))
    )
    (net (code "62") (name "Net-(rPI1A-Ethernet_Pair0_P)") (class "Default")
      (node (ref "H1") (pin "12") (pinfunction "12_12") (pintype "passive"))
      (node (ref "HA") (pin "11") (pinfunction "11_11") (pintype "passive"))
      (node (ref "rPI1") (pin "12") (pinfunction "Ethernet_Pair0_P_12") (pintype "passive"))
      (node (ref "rxPI1") (pin "12") (pinfunction "Ethernet_Pair0_P_12") (pintype "passive"))
    )
    (net (code "63") (name "Net-(rPI1A-Ethernet_Pair1_N)") (class "Default")
      (node (ref "H1") (pin "6") (pinfunction "6_6") (pintype "passive"))
      (node (ref "HA") (pin "5") (pinfunction "5_5") (pintype "passive"))
      (node (ref "rPI1") (pin "6") (pinfunction "Ethernet_Pair1_N_6") (pintype "passive"))
      (node (ref "rxPI1") (pin "6") (pinfunction "Ethernet_Pair1_N_6") (pintype "passive"))
    )
    (net (code "64") (name "Net-(rPI1A-Ethernet_Pair1_P)") (class "Default")
      (node (ref "H1") (pin "4") (pinfunction "4_4") (pintype "passive"))
      (node (ref "HA") (pin "3") (pinfunction "3_3") (pintype "passive"))
      (node (ref "rPI1") (pin "4") (pinfunction "Ethernet_Pair1_P_4") (pintype "passive"))
      (node (ref "rxPI1") (pin "4") (pinfunction "Ethernet_Pair1_P_4") (pintype "passive"))
    )
    (net (code "65") (name "Net-(rPI1A-Ethernet_Pair2_N)") (class "Default")
      (node (ref "H1") (pin "9") (pinfunction "9_9") (pintype "passive"))
      (node (ref "HA") (pin "10") (pinfunction "10_10") (pintype "passive"))
      (node (ref "rPI1") (pin "9") (pinfunction "Ethernet_Pair2_N_9") (pintype "passive"))
      (node (ref "rxPI1") (pin "9") (pinfunction "Ethernet_Pair2_N_9") (pintype "passive"))
    )
    (net (code "66") (name "Net-(rPI1A-Ethernet_Pair2_P)") (class "Default")
      (node (ref "H1") (pin "11") (pinfunction "11_11") (pintype "passive"))
      (node (ref "HA") (pin "12") (pinfunction "12_12") (pintype "passive"))
      (node (ref "rPI1") (pin "11") (pinfunction "Ethernet_Pair2_P_11") (pintype "passive"))
      (node (ref "rxPI1") (pin "11") (pinfunction "Ethernet_Pair2_P_11") (pintype "passive"))
    )
    (net (code "67") (name "Net-(rPI1A-Ethernet_Pair3_N)") (class "Default")
      (node (ref "H1") (pin "5") (pinfunction "5_5") (pintype "passive"))
      (node (ref "HA") (pin "6") (pinfunction "6_6") (pintype "passive"))
      (node (ref "rPI1") (pin "5") (pinfunction "Ethernet_Pair3_N_5") (pintype "passive"))
      (node (ref "rxPI1") (pin "5") (pinfunction "Ethernet_Pair3_N_5") (pintype "passive"))
    )
    (net (code "68") (name "Net-(rPI1A-Ethernet_Pair3_P)") (class "Default")
      (node (ref "H1") (pin "3") (pinfunction "3_3") (pintype "passive"))
      (node (ref "HA") (pin "4") (pinfunction "4_4") (pintype "passive"))
      (node (ref "rPI1") (pin "3") (pinfunction "Ethernet_Pair3_P_3") (pintype "passive"))
      (node (ref "rxPI1") (pin "3") (pinfunction "Ethernet_Pair3_P_3") (pintype "passive"))
    )
    (net (code "69") (name "Net-(rPI1A-Ethernet_SYNC_IN(1.8v))") (class "Default")
      (node (ref "H1") (pin "16") (pinfunction "16_16") (pintype "passive"))
      (node (ref "HA") (pin "15") (pinfunction "15_15") (pintype "passive"))
      (node (ref "rPI1") (pin "16") (pinfunction "Ethernet_SYNC_IN(1.8v)_16") (pintype "passive"))
      (node (ref "rxPI1") (pin "16") (pinfunction "Ethernet_SYNC_IN(1.8v)_16") (pintype "passive"))
    )
    (net (code "70") (name "Net-(rPI1A-Ethernet_SYNC_OUT(1.8v))") (class "Default")
      (node (ref "H1") (pin "18") (pinfunction "18_18") (pintype "passive"))
      (node (ref "HA") (pin "17") (pinfunction "17_17") (pintype "passive"))
      (node (ref "rPI1") (pin "18") (pinfunction "Ethernet_SYNC_OUT(1.8v)_18") (pintype "passive"))
      (node (ref "rxPI1") (pin "18") (pinfunction "Ethernet_SYNC_OUT(1.8v)_18") (pintype "passive"))
    )
    (net (code "71") (name "Net-(rPI1A-Ethernet_nLED2(3.3v))") (class "Default")
      (node (ref "H1") (pin "17") (pinfunction "17_17") (pintype "passive"))
      (node (ref "HA") (pin "18") (pinfunction "18_18") (pintype "passive"))
      (node (ref "rPI1") (pin "17") (pinfunction "Ethernet_nLED2(3.3v)_17") (pintype "passive"))
      (node (ref "rxPI1") (pin "17") (pinfunction "Ethernet_nLED2(3.3v)_17") (pintype "passive"))
    )
    (net (code "72") (name "Net-(rPI1A-Ethernet_nLED3(3.3v))") (class "Default")
      (node (ref "H1") (pin "15") (pinfunction "15_15") (pintype "passive"))
      (node (ref "HA") (pin "16") (pinfunction "16_16") (pintype "passive"))
      (node (ref "rPI1") (pin "15") (pinfunction "Ethernet_nLED3(3.3v)_15") (pintype "passive"))
      (node (ref "rxPI1") (pin "15") (pinfunction "Ethernet_nLED3(3.3v)_15") (pintype "passive"))
    )
    (net (code "73") (name "Net-(rPI1A-FAN_PWM)") (class "Default")
      (node (ref "H1") (pin "19") (pinfunction "19_19") (pintype "passive"))
      (node (ref "HA") (pin "20") (pinfunction "20_20") (pintype "passive"))
      (node (ref "rPI1") (pin "19") (pinfunction "FAN_PWM_19") (pintype "passive"))
      (node (ref "rxPI1") (pin "19") (pinfunction "Ethernet_nLED1(3.3v)_19") (pintype "passive"))
    )
    (net (code "74") (name "Net-(rPI1A-GPIO2)") (class "Default")
      (node (ref "H1") (pin "58") (pinfunction "58_58") (pintype "passive"))
      (node (ref "HA") (pin "57") (pinfunction "57_57") (pintype "passive"))
      (node (ref "rPI1") (pin "58") (pinfunction "GPIO2_58") (pintype "passive"))
      (node (ref "rxPI1") (pin "58") (pinfunction "GPIO2_58") (pintype "passive"))
    )
    (net (code "75") (name "Net-(rPI1A-GPIO3)") (class "Default")
      (node (ref "H1") (pin "56") (pinfunction "56_56") (pintype "passive"))
      (node (ref "HA") (pin "55") (pinfunction "55_55") (pintype "passive"))
      (node (ref "rPI1") (pin "56") (pinfunction "GPIO3_56") (pintype "passive"))
      (node (ref "rxPI1") (pin "56") (pinfunction "GPIO3_56") (pintype "passive"))
    )
    (net (code "76") (name "Net-(rPI1A-GPIO4)") (class "Default")
      (node (ref "H1") (pin "54") (pinfunction "54_54") (pintype "passive"))
      (node (ref "HA") (pin "53") (pinfunction "53_53") (pintype "passive"))
      (node (ref "rPI1") (pin "54") (pinfunction "GPIO4_54") (pintype "passive"))
      (node (ref "rxPI1") (pin "54") (pinfunction "GPIO4_54") (pintype "passive"))
    )
    (net (code "77") (name "Net-(rPI1A-GPIO5)") (class "Default")
      (node (ref "H1") (pin "34") (pinfunction "34_34") (pintype "passive"))
      (node (ref "HA") (pin "33") (pinfunction "33_33") (pintype "passive"))
      (node (ref "rPI1") (pin "34") (pinfunction "GPIO5_34") (pintype "passive"))
      (node (ref "rxPI1") (pin "34") (pinfunction "GPIO5_34") (pintype "passive"))
    )
    (net (code "78") (name "Net-(rPI1A-GPIO6)") (class "Default")
      (node (ref "H1") (pin "30") (pinfunction "30_30") (pintype "passive"))
      (node (ref "HA") (pin "29") (pinfunction "29_29") (pintype "passive"))
      (node (ref "rPI1") (pin "30") (pinfunction "GPIO6_30") (pintype "passive"))
      (node (ref "rxPI1") (pin "30") (pinfunction "GPIO6_30") (pintype "passive"))
    )
    (net (code "79") (name "Net-(rPI1A-GPIO7)") (class "Default")
      (node (ref "H1") (pin "37") (pinfunction "37_37") (pintype "passive"))
      (node (ref "HA") (pin "38") (pinfunction "38_38") (pintype "passive"))
      (node (ref "rPI1") (pin "37") (pinfunction "GPIO7_37") (pintype "passive"))
      (node (ref "rxPI1") (pin "37") (pinfunction "GPIO7_37") (pintype "passive"))
    )
    (net (code "80") (name "Net-(rPI1A-GPIO8)") (class "Default")
      (node (ref "H1") (pin "39") (pinfunction "39_39") (pintype "passive"))
      (node (ref "HA") (pin "40") (pinfunction "40_40") (pintype "passive"))
      (node (ref "rPI1") (pin "39") (pinfunction "GPIO8_39") (pintype "passive"))
      (node (ref "rxPI1") (pin "39") (pinfunction "GPIO8_39") (pintype "passive"))
    )
    (net (code "81") (name "Net-(rPI1A-GPIO9)") (class "Default")
      (node (ref "H1") (pin "40") (pinfunction "40_40") (pintype "passive"))
      (node (ref "HA") (pin "39") (pinfunction "39_39") (pintype "passive"))
      (node (ref "rPI1") (pin "40") (pinfunction "GPIO9_40") (pintype "passive"))
      (node (ref "rxPI1") (pin "40") (pinfunction "GPIO9_40") (pintype "passive"))
    )
    (net (code "82") (name "Net-(rPI1A-GPIO10)") (class "Default")
      (node (ref "H1") (pin "44") (pinfunction "44_44") (pintype "passive"))
      (node (ref "HA") (pin "43") (pinfunction "43_43") (pintype "passive"))
      (node (ref "rPI1") (pin "44") (pinfunction "GPIO10_44") (pintype "passive"))
      (node (ref "rxPI1") (pin "44") (pinfunction "GPIO10_44") (pintype "passive"))
    )
    (net (code "83") (name "Net-(rPI1A-GPIO11)") (class "Default")
      (node (ref "H1") (pin "38") (pinfunction "38_38") (pintype "passive"))
      (node (ref "HA") (pin "37") (pinfunction "37_37") (pintype "passive"))
      (node (ref "rPI1") (pin "38") (pinfunction "GPIO11_38") (pintype "passive"))
      (node (ref "rxPI1") (pin "38") (pinfunction "GPIO11_38") (pintype "passive"))
    )
    (net (code "84") (name "Net-(rPI1A-GPIO12)") (class "Default")
      (node (ref "H1") (pin "31") (pinfunction "31_31") (pintype "passive"))
      (node (ref "HA") (pin "32") (pinfunction "32_32") (pintype "passive"))
      (node (ref "rPI1") (pin "31") (pinfunction "GPIO12_31") (pintype "passive"))
      (node (ref "rxPI1") (pin "31") (pinfunction "GPIO12_31") (pintype "passive"))
    )
    (net (code "85") (name "Net-(rPI1A-GPIO13)") (class "Default")
      (node (ref "H1") (pin "28") (pinfunction "28_28") (pintype "passive"))
      (node (ref "HA") (pin "27") (pinfunction "27_27") (pintype "passive"))
      (node (ref "rPI1") (pin "28") (pinfunction "GPIO13_28") (pintype "passive"))
      (node (ref "rxPI1") (pin "28") (pinfunction "GPIO13_28") (pintype "passive"))
    )
    (net (code "86") (name "Net-(rPI1A-GPIO14)") (class "Default")
      (node (ref "H1") (pin "55") (pinfunction "55_55") (pintype "passive"))
      (node (ref "HA") (pin "56") (pinfunction "56_56") (pintype "passive"))
      (node (ref "rPI1") (pin "55") (pinfunction "GPIO14_55") (pintype "passive"))
      (node (ref "rxPI1") (pin "55") (pinfunction "GPIO14_55") (pintype "passive"))
    )
    (net (code "87") (name "Net-(rPI1A-GPIO15)") (class "Default")
      (node (ref "H1") (pin "51") (pinfunction "51_51") (pintype "passive"))
      (node (ref "HA") (pin "52") (pinfunction "52_52") (pintype "passive"))
      (node (ref "rPI1") (pin "51") (pinfunction "GPIO15_51") (pintype "passive"))
      (node (ref "rxPI1") (pin "51") (pinfunction "GPIO15_51") (pintype "passive"))
    )
    (net (code "88") (name "Net-(rPI1A-GPIO16)") (class "Default")
      (node (ref "H1") (pin "29") (pinfunction "29_29") (pintype "passive"))
      (node (ref "HA") (pin "30") (pinfunction "30_30") (pintype "passive"))
      (node (ref "rPI1") (pin "29") (pinfunction "GPIO16_29") (pintype "passive"))
      (node (ref "rxPI1") (pin "29") (pinfunction "GPIO16_29") (pintype "passive"))
    )
    (net (code "89") (name "Net-(rPI1A-GPIO17)") (class "Default")
      (node (ref "H1") (pin "50") (pinfunction "50_50") (pintype "passive"))
      (node (ref "HA") (pin "49") (pinfunction "49_49") (pintype "passive"))
      (node (ref "rPI1") (pin "50") (pinfunction "GPIO17_50") (pintype "passive"))
      (node (ref "rxPI1") (pin "50") (pinfunction "GPIO17_50") (pintype "passive"))
    )
    (net (code "90") (name "Net-(rPI1A-GPIO18)") (class "Default")
      (node (ref "H1") (pin "49") (pinfunction "49_49") (pintype "passive"))
      (node (ref "HA") (pin "50") (pinfunction "50_50") (pintype "passive"))
      (node (ref "rPI1") (pin "49") (pinfunction "GPIO18_49") (pintype "passive"))
      (node (ref "rxPI1") (pin "49") (pinfunction "GPIO18_49") (pintype "passive"))
    )
    (net (code "91") (name "Net-(rPI1A-GPIO19)") (class "Default")
      (node (ref "H1") (pin "26") (pinfunction "26_26") (pintype "passive"))
      (node (ref "HA") (pin "25") (pinfunction "25_25") (pintype "passive"))
      (node (ref "rPI1") (pin "26") (pinfunction "GPIO19_26") (pintype "passive"))
      (node (ref "rxPI1") (pin "26") (pinfunction "GPIO19_26") (pintype "passive"))
    )
    (net (code "92") (name "Net-(rPI1A-GPIO20)") (class "Default")
      (node (ref "H1") (pin "27") (pinfunction "27_27") (pintype "passive"))
      (node (ref "HA") (pin "28") (pinfunction "28_28") (pintype "passive"))
      (node (ref "rPI1") (pin "27") (pinfunction "GPIO20_27") (pintype "passive"))
      (node (ref "rxPI1") (pin "27") (pinfunction "GPIO20_27") (pintype "passive"))
    )
    (net (code "93") (name "Net-(rPI1A-GPIO21)") (class "Default")
      (node (ref "H1") (pin "25") (pinfunction "25_25") (pintype "passive"))
      (node (ref "HA") (pin "26") (pinfunction "26_26") (pintype "passive"))
      (node (ref "rPI1") (pin "25") (pinfunction "GPIO21_25") (pintype "passive"))
      (node (ref "rxPI1") (pin "25") (pinfunction "GPIO21_25") (pintype "passive"))
    )
    (net (code "94") (name "Net-(rPI1A-GPIO22)") (class "Default")
      (node (ref "H1") (pin "46") (pinfunction "46_46") (pintype "passive"))
      (node (ref "HA") (pin "45") (pinfunction "45_45") (pintype "passive"))
      (node (ref "rPI1") (pin "46") (pinfunction "GPIO22_46") (pintype "passive"))
      (node (ref "rxPI1") (pin "46") (pinfunction "GPIO22_46") (pintype "passive"))
    )
    (net (code "95") (name "Net-(rPI1A-GPIO23)") (class "Default")
      (node (ref "H1") (pin "47") (pinfunction "47_47") (pintype "passive"))
      (node (ref "HA") (pin "48") (pinfunction "48_48") (pintype "passive"))
      (node (ref "rPI1") (pin "47") (pinfunction "GPIO23_47") (pintype "passive"))
      (node (ref "rxPI1") (pin "47") (pinfunction "GPIO23_47") (pintype "passive"))
    )
    (net (code "96") (name "Net-(rPI1A-GPIO24)") (class "Default")
      (node (ref "H1") (pin "45") (pinfunction "45_45") (pintype "passive"))
      (node (ref "HA") (pin "46") (pinfunction "46_46") (pintype "passive"))
      (node (ref "rPI1") (pin "45") (pinfunction "GPIO24_45") (pintype "passive"))
      (node (ref "rxPI1") (pin "45") (pinfunction "GPIO24_45") (pintype "passive"))
    )
    (net (code "97") (name "Net-(rPI1A-GPIO25)") (class "Default")
      (node (ref "H1") (pin "41") (pinfunction "41_41") (pintype "passive"))
      (node (ref "HA") (pin "42") (pinfunction "42_42") (pintype "passive"))
      (node (ref "rPI1") (pin "41") (pinfunction "GPIO25_41") (pintype "passive"))
      (node (ref "rxPI1") (pin "41") (pinfunction "GPIO25_41") (pintype "passive"))
    )
    (net (code "98") (name "Net-(rPI1A-GPIO26)") (class "Default")
      (node (ref "H1") (pin "24") (pinfunction "24_24") (pintype "passive"))
      (node (ref "HA") (pin "23") (pinfunction "23_23") (pintype "passive"))
      (node (ref "rPI1") (pin "24") (pinfunction "GPIO26_24") (pintype "passive"))
      (node (ref "rxPI1") (pin "24") (pinfunction "GPIO26_24") (pintype "passive"))
    )
    (net (code "99") (name "Net-(rPI1A-GPIO27)") (class "Default")
      (node (ref "H1") (pin "48") (pinfunction "48_48") (pintype "passive"))
      (node (ref "HA") (pin "47") (pinfunction "47_47") (pintype "passive"))
      (node (ref "rPI1") (pin "48") (pinfunction "GPIO27_48") (pintype "passive"))
      (node (ref "rxPI1") (pin "48") (pinfunction "GPIO27_48") (pintype "passive"))
    )
    (net (code "100") (name "Net-(rPI1A-GPIO_VREF(1.8v{slash}3.3v_Input))") (class "Default")
      (node (ref "H1") (pin "78") (pinfunction "78_78") (pintype "passive"))
      (node (ref "HA") (pin "77") (pinfunction "77_77") (pintype "passive"))
      (node (ref "rPI1") (pin "78") (pinfunction "GPIO_VREF(1.8v/3.3v_Input)_78") (pintype "passive"))
      (node (ref "rxPI1") (pin "78") (pinfunction "GPIO_VREF(1.8v/3.3v_Input)_78") (pintype "passive"))
    )
    (net (code "101") (name "Net-(rPI1A-Global_EN)") (class "Default")
      (node (ref "H1") (pin "99") (pinfunction "99_99") (pintype "passive"))
      (node (ref "HA") (pin "100") (pinfunction "100_100") (pintype "passive"))
      (node (ref "rPI1") (pin "99") (pinfunction "Global_EN_99") (pintype "passive"))
      (node (ref "rxPI1") (pin "99") (pinfunction "Global_EN_99") (pintype "passive"))
    )
    (net (code "102") (name "Net-(rPI1A-ID_SC)") (class "Default")
      (node (ref "H1") (pin "35") (pinfunction "35_35") (pintype "passive"))
      (node (ref "HA") (pin "36") (pinfunction "36_36") (pintype "passive"))
      (node (ref "rPI1") (pin "35") (pinfunction "ID_SC_35") (pintype "passive"))
      (node (ref "rxPI1") (pin "35") (pinfunction "ID_SC_35") (pintype "passive"))
    )
    (net (code "103") (name "Net-(rPI1A-ID_SD)") (class "Default")
      (node (ref "H1") (pin "36") (pinfunction "36_36") (pintype "passive"))
      (node (ref "HA") (pin "35") (pinfunction "35_35") (pintype "passive"))
      (node (ref "rPI1") (pin "36") (pinfunction "ID_SD_36") (pintype "passive"))
      (node (ref "rxPI1") (pin "36") (pinfunction "ID_SD_36") (pintype "passive"))
    )
    (net (code "104") (name "Net-(rPI1A-PI_nLED_Activity)") (class "Default")
      (node (ref "H1") (pin "21") (pinfunction "21_21") (pintype "passive"))
      (node (ref "HA") (pin "22") (pinfunction "22_22") (pintype "passive"))
      (node (ref "rPI1") (pin "21") (pinfunction "PI_nLED_Activity_21") (pintype "passive"))
      (node (ref "rxPI1") (pin "21") (pinfunction "PI_nLED_Activity_21") (pintype "passive"))
    )
    (net (code "105") (name "Net-(rPI1A-RUN_PG)") (class "Default")
      (node (ref "H1") (pin "92") (pinfunction "92_92") (pintype "passive"))
      (node (ref "HA") (pin "91") (pinfunction "91_91") (pintype "passive"))
      (node (ref "rPI1") (pin "92") (pinfunction "RUN_PG_92") (pintype "passive"))
      (node (ref "rxPI1") (pin "92") (pinfunction "RUN_PG_92") (pintype "passive"))
    )
    (net (code "106") (name "Net-(rPI1A-Reserved)") (class "Default")
      (node (ref "H1") (pin "76") (pinfunction "76_76") (pintype "passive"))
      (node (ref "HA") (pin "75") (pinfunction "75_75") (pintype "passive"))
      (node (ref "rPI1") (pin "76") (pinfunction "Reserved_76") (pintype "passive"))
      (node (ref "rxPI1") (pin "76") (pinfunction "Reserved_76") (pintype "passive"))
    )
    (net (code "107") (name "Net-(rPI1A-SCL0)") (class "Default")
      (node (ref "H1") (pin "80") (pinfunction "80_80") (pintype "passive"))
      (node (ref "HA") (pin "79") (pinfunction "79_79") (pintype "passive"))
      (node (ref "rPI1") (pin "80") (pinfunction "SCL0_80") (pintype "passive"))
      (node (ref "rxPI1") (pin "80") (pinfunction "SCL0_80") (pintype "passive"))
    )
    (net (code "108") (name "Net-(rPI1A-SDA0)") (class "Default")
      (node (ref "H1") (pin "82") (pinfunction "82_82") (pintype "passive"))
      (node (ref "HA") (pin "81") (pinfunction "81_81") (pintype "passive"))
      (node (ref "rPI1") (pin "82") (pinfunction "SDA0_82") (pintype "passive"))
      (node (ref "rxPI1") (pin "82") (pinfunction "SDA0_82") (pintype "passive"))
    )
    (net (code "109") (name "Net-(rPI1A-SD_CLK)") (class "Default")
      (node (ref "H1") (pin "57") (pinfunction "57_57") (pintype "passive"))
      (node (ref "HA") (pin "58") (pinfunction "58_58") (pintype "passive"))
      (node (ref "rPI1") (pin "57") (pinfunction "SD_CLK_57") (pintype "passive"))
      (node (ref "rxPI1") (pin "57") (pinfunction "SD_CLK_57") (pintype "passive"))
    )
    (net (code "110") (name "Net-(rPI1A-SD_CMD)") (class "Default")
      (node (ref "H1") (pin "62") (pinfunction "62_62") (pintype "passive"))
      (node (ref "HA") (pin "61") (pinfunction "61_61") (pintype "passive"))
      (node (ref "rPI1") (pin "62") (pinfunction "SD_CMD_62") (pintype "passive"))
      (node (ref "rxPI1") (pin "62") (pinfunction "SD_CMD_62") (pintype "passive"))
    )
    (net (code "111") (name "Net-(rPI1A-SD_DAT0)") (class "Default")
      (node (ref "H1") (pin "63") (pinfunction "63_63") (pintype "passive"))
      (node (ref "HA") (pin "64") (pinfunction "64_64") (pintype "passive"))
      (node (ref "rPI1") (pin "63") (pinfunction "SD_DAT0_63") (pintype "passive"))
      (node (ref "rxPI1") (pin "63") (pinfunction "SD_DAT0_63") (pintype "passive"))
    )
    (net (code "112") (name "Net-(rPI1A-SD_DAT1)") (class "Default")
      (node (ref "H1") (pin "67") (pinfunction "67_67") (pintype "passive"))
      (node (ref "HA") (pin "68") (pinfunction "68_68") (pintype "passive"))
      (node (ref "rPI1") (pin "67") (pinfunction "SD_DAT1_67") (pintype "passive"))
      (node (ref "rxPI1") (pin "67") (pinfunction "SD_DAT1_67") (pintype "passive"))
    )
    (net (code "113") (name "Net-(rPI1A-SD_DAT2)") (class "Default")
      (node (ref "H1") (pin "69") (pinfunction "69_69") (pintype "passive"))
      (node (ref "HA") (pin "70") (pinfunction "70_70") (pintype "passive"))
      (node (ref "rPI1") (pin "69") (pinfunction "SD_DAT2_69") (pintype "passive"))
      (node (ref "rxPI1") (pin "69") (pinfunction "SD_DAT2_69") (pintype "passive"))
    )
    (net (code "114") (name "Net-(rPI1A-SD_DAT3)") (class "Default")
      (node (ref "H1") (pin "61") (pinfunction "61_61") (pintype "passive"))
      (node (ref "HA") (pin "62") (pinfunction "62_62") (pintype "passive"))
      (node (ref "rPI1") (pin "61") (pinfunction "SD_DAT3_61") (pintype "passive"))
      (node (ref "rxPI1") (pin "61") (pinfunction "SD_DAT3_61") (pintype "passive"))
    )
    (net (code "115") (name "Net-(rPI1A-SD_DAT4)") (class "Default")
      (node (ref "H1") (pin "68") (pinfunction "68_68") (pintype "passive"))
      (node (ref "HA") (pin "67") (pinfunction "67_67") (pintype "passive"))
      (node (ref "rPI1") (pin "68") (pinfunction "SD_DAT4_68") (pintype "passive"))
      (node (ref "rxPI1") (pin "68") (pinfunction "SD_DAT4_68") (pintype "passive"))
    )
    (net (code "116") (name "Net-(rPI1A-SD_DAT5)") (class "Default")
      (node (ref "H1") (pin "64") (pinfunction "64_64") (pintype "passive"))
      (node (ref "HA") (pin "63") (pinfunction "63_63") (pintype "passive"))
      (node (ref "rPI1") (pin "64") (pinfunction "SD_DAT5_64") (pintype "passive"))
      (node (ref "rxPI1") (pin "64") (pinfunction "SD_DAT5_64") (pintype "passive"))
    )
    (net (code "117") (name "Net-(rPI1A-SD_DAT6)") (class "Default")
      (node (ref "H1") (pin "72") (pinfunction "72_72") (pintype "passive"))
      (node (ref "HA") (pin "71") (pinfunction "71_71") (pintype "passive"))
      (node (ref "rPI1") (pin "72") (pinfunction "SD_DAT6_72") (pintype "passive"))
      (node (ref "rxPI1") (pin "72") (pinfunction "SD_DAT6_72") (pintype "passive"))
    )
    (net (code "118") (name "Net-(rPI1A-SD_DAT7)") (class "Default")
      (node (ref "H1") (pin "70") (pinfunction "70_70") (pintype "passive"))
      (node (ref "HA") (pin "69") (pinfunction "69_69") (pintype "passive"))
      (node (ref "rPI1") (pin "70") (pinfunction "SD_DAT7_70") (pintype "passive"))
      (node (ref "rxPI1") (pin "70") (pinfunction "SD_DAT7_70") (pintype "passive"))
    )
    (net (code "119") (name "Net-(rPI1A-SD_PWR_ON)") (class "Default")
      (node (ref "H1") (pin "75") (pinfunction "75_75") (pintype "passive"))
      (node (ref "HA") (pin "76") (pinfunction "76_76") (pintype "passive"))
      (node (ref "rPI1") (pin "75") (pinfunction "SD_PWR_ON_75") (pintype "passive"))
      (node (ref "rxPI1") (pin "75") (pinfunction "SD_PWR_ON_75") (pintype "passive"))
    )
    (net (code "120") (name "Net-(rPI1A-SD_VDD_Override)") (class "Default")
      (node (ref "H1") (pin "73") (pinfunction "73_73") (pintype "passive"))
      (node (ref "HA") (pin "74") (pinfunction "74_74") (pintype "passive"))
      (node (ref "rPI1") (pin "73") (pinfunction "SD_VDD_Override_73") (pintype "passive"))
      (node (ref "rxPI1") (pin "73") (pinfunction "SD_VDD_Override_73") (pintype "passive"))
    )
    (net (code "121") (name "Net-(rPI1A-WiFi_nDisable)") (class "Default")
      (node (ref "H1") (pin "89") (pinfunction "89_89") (pintype "passive"))
      (node (ref "HA") (pin "90") (pinfunction "90_90") (pintype "passive"))
      (node (ref "rPI1") (pin "89") (pinfunction "WiFi_nDisable_89") (pintype "passive"))
      (node (ref "rxPI1") (pin "89") (pinfunction "WiFi_nDisable_89") (pintype "passive"))
    )
    (net (code "122") (name "Net-(rPI1A-nPI_LED_PWR)") (class "Default")
      (node (ref "H1") (pin "95") (pinfunction "95_95") (pintype "passive"))
      (node (ref "HA") (pin "96") (pinfunction "96_96") (pintype "passive"))
      (node (ref "rPI1") (pin "95") (pinfunction "nPI_LED_PWR_95") (pintype "passive"))
      (node (ref "rxPI1") (pin "95") (pinfunction "nPI_LED_PWR_95") (pintype "passive"))
    )
    (net (code "123") (name "Net-(rPI1A-nRPIBOOT)") (class "Default")
      (node (ref "H1") (pin "93") (pinfunction "93_93") (pintype "passive"))
      (node (ref "HA") (pin "94") (pinfunction "94_94") (pintype "passive"))
      (node (ref "rPI1") (pin "93") (pinfunction "nRPIBOOT_93") (pintype "passive"))
      (node (ref "rxPI1") (pin "93") (pinfunction "nRPIBOOT_93") (pintype "passive"))
    )
    (net (code "124") (name "Net-(rPI1B-MIPI0_C_N)") (class "Default")
      (node (ref "HB") (pin "28") (pinfunction "28_28") (pintype "passive"))
      (node (ref "rPI1") (pin "127") (pinfunction "MIPI0_C_N_127") (pintype "passive"))
    )
    (net (code "125") (name "Net-(rPI1B-MIPI0_C_P)") (class "Default")
      (node (ref "HB") (pin "30") (pinfunction "30_30") (pintype "passive"))
      (node (ref "rPI1") (pin "129") (pinfunction "MIPI0_C_P_129") (pintype "passive"))
    )
    (net (code "126") (name "Net-(rPI1B-MIPI0_D0_N)") (class "Default")
      (node (ref "HB") (pin "16") (pinfunction "16_16") (pintype "passive"))
      (node (ref "rPI1") (pin "115") (pinfunction "MIPI0_D0_N_115") (pintype "passive"))
    )
    (net (code "127") (name "Net-(rPI1B-MIPI0_D0_P)") (class "Default")
      (node (ref "HB") (pin "18") (pinfunction "18_18") (pintype "passive"))
      (node (ref "rPI1") (pin "117") (pinfunction "MIPI0_D0_P_117") (pintype "passive"))
    )
    (net (code "128") (name "Net-(rPI1B-MIPI0_D1_N)") (class "Default")
      (node (ref "HB") (pin "22") (pinfunction "22_22") (pintype "passive"))
      (node (ref "rPI1") (pin "121") (pinfunction "MIPI0_D1_N_121") (pintype "passive"))
    )
    (net (code "129") (name "Net-(rPI1B-MIPI0_D1_P)") (class "Default")
      (node (ref "HB") (pin "24") (pinfunction "24_24") (pintype "passive"))
      (node (ref "rPI1") (pin "123") (pinfunction "MIPI0_D1_P_123") (pintype "passive"))
    )
    (net (code "130") (name "Net-(rPI1B-MIPI0_D2_N)") (class "Default")
      (node (ref "HB") (pin "34") (pinfunction "34_34") (pintype "passive"))
      (node (ref "rPI1") (pin "133") (pinfunction "MIPI0_D2_N_133") (pintype "passive"))
    )
    (net (code "131") (name "Net-(rPI1B-MIPI0_D2_P)") (class "Default")
      (node (ref "HB") (pin "36") (pinfunction "36_36") (pintype "passive"))
      (node (ref "rPI1") (pin "135") (pinfunction "MIPI0_D2_P_135") (pintype "passive"))
    )
    (net (code "132") (name "Net-(rPI1B-MIPI0_D3_N)") (class "Default")
      (node (ref "HB") (pin "40") (pinfunction "40_40") (pintype "passive"))
      (node (ref "rPI1") (pin "139") (pinfunction "MIPI0_D3_N_139") (pintype "passive"))
    )
    (net (code "133") (name "Net-(rPI1B-MIPI0_D3_P)") (class "Default")
      (node (ref "HB") (pin "42") (pinfunction "42_42") (pintype "passive"))
      (node (ref "rPI1") (pin "141") (pinfunction "MIPI0_D3_P_141") (pintype "passive"))
    )
    (net (code "134") (name "Net-(rPI1B-MIPI1_C_N)") (class "Default")
      (node (ref "HB") (pin "88") (pinfunction "88_88") (pintype "passive"))
      (node (ref "rPI1") (pin "187") (pinfunction "MIPI1_C_N_187") (pintype "passive"))
    )
    (net (code "135") (name "Net-(rPI1B-MIPI1_C_P)") (class "Default")
      (node (ref "HB") (pin "90") (pinfunction "90_90") (pintype "passive"))
      (node (ref "rPI1") (pin "189") (pinfunction "MIPI1_C_P_189") (pintype "passive"))
    )
    (net (code "136") (name "Net-(rPI1B-MIPI1_D0_N)") (class "Default")
      (node (ref "HB") (pin "76") (pinfunction "76_76") (pintype "passive"))
      (node (ref "rPI1") (pin "175") (pinfunction "MIPI1_D0_N_175") (pintype "passive"))
    )
    (net (code "137") (name "Net-(rPI1B-MIPI1_D0_P)") (class "Default")
      (node (ref "HB") (pin "78") (pinfunction "78_78") (pintype "passive"))
      (node (ref "rPI1") (pin "177") (pinfunction "MIPI1_D0_P_177") (pintype "passive"))
    )
    (net (code "138") (name "Net-(rPI1B-MIPI1_D1_N)") (class "Default")
      (node (ref "HB") (pin "82") (pinfunction "82_82") (pintype "passive"))
      (node (ref "rPI1") (pin "181") (pinfunction "MIPI1_D1_N_181") (pintype "passive"))
    )
    (net (code "139") (name "Net-(rPI1B-MIPI1_D1_P)") (class "Default")
      (node (ref "HB") (pin "84") (pinfunction "84_84") (pintype "passive"))
      (node (ref "rPI1") (pin "183") (pinfunction "MIPI1_D1_P_183") (pintype "passive"))
    )
    (net (code "140") (name "Net-(rPI1B-MIPI1_D2_N)") (class "Default")
      (node (ref "HB") (pin "94") (pinfunction "94_94") (pintype "passive"))
      (node (ref "rPI1") (pin "193") (pinfunction "MIPI1_D2_N_193") (pintype "passive"))
    )
    (net (code "141") (name "Net-(rPI1B-MIPI1_D2_P)") (class "Default")
      (node (ref "HB") (pin "96") (pinfunction "96_96") (pintype "passive"))
      (node (ref "rPI1") (pin "195") (pinfunction "MIPI1_D2_P_195") (pintype "passive"))
    )
    (net (code "142") (name "Net-(rPI1B-MIPI1_D3_N)") (class "Default")
      (node (ref "HB") (pin "93") (pinfunction "93_93") (pintype "passive"))
      (node (ref "rPI1") (pin "194") (pinfunction "MIPI1_D3_N_194") (pintype "passive"))
    )
    (net (code "143") (name "Net-(rPI1B-MIPI1_D3_P)") (class "Default")
      (node (ref "HB") (pin "95") (pinfunction "95_95") (pintype "passive"))
      (node (ref "rPI1") (pin "196") (pinfunction "MIPI1_D3_P_196") (pintype "passive"))
    )
    (net (code "144") (name "Net-(rPI1B-VBUS_EN)") (class "Default")
      (node (ref "HB") (pin "12") (pinfunction "12_12") (pintype "passive"))
      (node (ref "rPI1") (pin "111") (pinfunction "VBUS_EN_111") (pintype "passive"))
    )
    (net (code "145") (name "Net-(rxPI1B-CAM0_C_N)") (class "Default")
      (node (ref "H2") (pin "40") (pinfunction "40_40") (pintype "passive"))
      (node (ref "rxPI1") (pin "140") (pinfunction "CAM0_C_N_140") (pintype "passive"))
    )
    (net (code "146") (name "Net-(rxPI1B-CAM0_C_P)") (class "Default")
      (node (ref "H2") (pin "42") (pinfunction "42_42") (pintype "passive"))
      (node (ref "rxPI1") (pin "142") (pinfunction "CAM0_C_P_142") (pintype "passive"))
    )
    (net (code "147") (name "Net-(rxPI1B-CAM0_D0_N)") (class "Default")
      (node (ref "H2") (pin "28") (pinfunction "28_28") (pintype "passive"))
      (node (ref "rxPI1") (pin "128") (pinfunction "CAM0_D0_N_128") (pintype "passive"))
    )
    (net (code "148") (name "Net-(rxPI1B-CAM0_D0_P)") (class "Default")
      (node (ref "H2") (pin "30") (pinfunction "30_30") (pintype "passive"))
      (node (ref "rxPI1") (pin "130") (pinfunction "CAM0_D0_P_130") (pintype "passive"))
    )
    (net (code "149") (name "Net-(rxPI1B-CAM0_D1_N)") (class "Default")
      (node (ref "H2") (pin "34") (pinfunction "34_34") (pintype "passive"))
      (node (ref "rxPI1") (pin "134") (pinfunction "CAM0_D1_N_134") (pintype "passive"))
    )
    (net (code "150") (name "Net-(rxPI1B-CAM0_D1_P)") (class "Default")
      (node (ref "H2") (pin "36") (pinfunction "36_36") (pintype "passive"))
      (node (ref "rxPI1") (pin "136") (pinfunction "CAM0_D1_P_136") (pintype "passive"))
    )
    (net (code "151") (name "Net-(rxPI1B-CAM1_C_N)") (class "Default")
      (node (ref "H2") (pin "27") (pinfunction "27_27") (pintype "passive"))
      (node (ref "rxPI1") (pin "127") (pinfunction "CAM1_C_N_127") (pintype "passive"))
    )
    (net (code "152") (name "Net-(rxPI1B-CAM1_C_P)") (class "Default")
      (node (ref "H2") (pin "29") (pinfunction "29_29") (pintype "passive"))
      (node (ref "rxPI1") (pin "129") (pinfunction "CAM1_C_P_129") (pintype "passive"))
    )
    (net (code "153") (name "Net-(rxPI1B-CAM1_D0_N)") (class "Default")
      (node (ref "H2") (pin "15") (pinfunction "15_15") (pintype "passive"))
      (node (ref "rxPI1") (pin "115") (pinfunction "CAM1_D0_N_115") (pintype "passive"))
    )
    (net (code "154") (name "Net-(rxPI1B-CAM1_D0_P)") (class "Default")
      (node (ref "H2") (pin "17") (pinfunction "17_17") (pintype "passive"))
      (node (ref "rxPI1") (pin "117") (pinfunction "CAM1_D0_P_117") (pintype "passive"))
    )
    (net (code "155") (name "Net-(rxPI1B-CAM1_D1_N)") (class "Default")
      (node (ref "H2") (pin "21") (pinfunction "21_21") (pintype "passive"))
      (node (ref "rxPI1") (pin "121") (pinfunction "CAM1_D1_N_121") (pintype "passive"))
    )
    (net (code "156") (name "Net-(rxPI1B-CAM1_D1_P)") (class "Default")
      (node (ref "H2") (pin "23") (pinfunction "23_23") (pintype "passive"))
      (node (ref "rxPI1") (pin "123") (pinfunction "CAM1_D1_P_123") (pintype "passive"))
    )
    (net (code "157") (name "Net-(rxPI1B-CAM1_D2_N)") (class "Default")
      (node (ref "H2") (pin "33") (pinfunction "33_33") (pintype "passive"))
      (node (ref "rxPI1") (pin "133") (pinfunction "CAM1_D2_N_133") (pintype "passive"))
    )
    (net (code "158") (name "Net-(rxPI1B-CAM1_D2_P)") (class "Default")
      (node (ref "H2") (pin "35") (pinfunction "35_35") (pintype "passive"))
      (node (ref "rxPI1") (pin "135") (pinfunction "CAM1_D2_P_135") (pintype "passive"))
    )
    (net (code "159") (name "Net-(rxPI1B-CAM1_D3_N)") (class "Default")
      (node (ref "H2") (pin "39") (pinfunction "39_39") (pintype "passive"))
      (node (ref "rxPI1") (pin "139") (pinfunction "CAM1_D3_N_139") (pintype "passive"))
    )
    (net (code "160") (name "Net-(rxPI1B-CAM1_D3_P)") (class "Default")
      (node (ref "H2") (pin "41") (pinfunction "41_41") (pintype "passive"))
      (node (ref "rxPI1") (pin "141") (pinfunction "CAM1_D3_P_141") (pintype "passive"))
    )
    (net (code "161") (name "Net-(rxPI1B-DSI0_C_N)") (class "Default")
      (node (ref "H2") (pin "69") (pinfunction "69_69") (pintype "passive"))
      (node (ref "rxPI1") (pin "169") (pinfunction "DSI0_C_N_169") (pintype "passive"))
    )
    (net (code "162") (name "Net-(rxPI1B-DSI0_C_P)") (class "Default")
      (node (ref "H2") (pin "71") (pinfunction "71_71") (pintype "passive"))
      (node (ref "rxPI1") (pin "171") (pinfunction "DSI0_C_P_171") (pintype "passive"))
    )
    (net (code "163") (name "Net-(rxPI1B-DSI0_D0_N)") (class "Default")
      (node (ref "H2") (pin "57") (pinfunction "57_57") (pintype "passive"))
      (node (ref "rxPI1") (pin "157") (pinfunction "DSI0_D0_N_157") (pintype "passive"))
    )
    (net (code "164") (name "Net-(rxPI1B-DSI0_D0_P)") (class "Default")
      (node (ref "H2") (pin "59") (pinfunction "59_59") (pintype "passive"))
      (node (ref "rxPI1") (pin "159") (pinfunction "DSI0_D0_P_159") (pintype "passive"))
    )
    (net (code "165") (name "Net-(rxPI1B-DSI0_D1_N)") (class "Default")
      (node (ref "H2") (pin "63") (pinfunction "63_63") (pintype "passive"))
      (node (ref "rxPI1") (pin "163") (pinfunction "DSI0_D1_N_163") (pintype "passive"))
    )
    (net (code "166") (name "Net-(rxPI1B-DSI0_D1_P)") (class "Default")
      (node (ref "H2") (pin "65") (pinfunction "65_65") (pintype "passive"))
      (node (ref "rxPI1") (pin "165") (pinfunction "DSI0_D1_P_165") (pintype "passive"))
    )
    (net (code "167") (name "Net-(rxPI1B-DSI1_C_N)") (class "Default")
      (node (ref "H2") (pin "87") (pinfunction "87_87") (pintype "passive"))
      (node (ref "rxPI1") (pin "187") (pinfunction "DSI1_C_N_187") (pintype "passive"))
    )
    (net (code "168") (name "Net-(rxPI1B-DSI1_C_P)") (class "Default")
      (node (ref "H2") (pin "89") (pinfunction "89_89") (pintype "passive"))
      (node (ref "rxPI1") (pin "189") (pinfunction "DSI1_C_P_189") (pintype "passive"))
    )
    (net (code "169") (name "Net-(rxPI1B-DSI1_D0_N)") (class "Default")
      (node (ref "H2") (pin "75") (pinfunction "75_75") (pintype "passive"))
      (node (ref "rxPI1") (pin "175") (pinfunction "DSI1_D0_N_175") (pintype "passive"))
    )
    (net (code "170") (name "Net-(rxPI1B-DSI1_D0_P)") (class "Default")
      (node (ref "H2") (pin "77") (pinfunction "77_77") (pintype "passive"))
      (node (ref "rxPI1") (pin "177") (pinfunction "DSI1_D0_P_177") (pintype "passive"))
    )
    (net (code "171") (name "Net-(rxPI1B-DSI1_D1_N)") (class "Default")
      (node (ref "H2") (pin "81") (pinfunction "81_81") (pintype "passive"))
      (node (ref "rxPI1") (pin "181") (pinfunction "DSI1_D1_N_181") (pintype "passive"))
    )
    (net (code "172") (name "Net-(rxPI1B-DSI1_D1_P)") (class "Default")
      (node (ref "H2") (pin "83") (pinfunction "83_83") (pintype "passive"))
      (node (ref "rxPI1") (pin "183") (pinfunction "DSI1_D1_P_183") (pintype "passive"))
    )
    (net (code "173") (name "Net-(rxPI1B-DSI1_D2_N)") (class "Default")
      (node (ref "H2") (pin "93") (pinfunction "93_93") (pintype "passive"))
      (node (ref "rxPI1") (pin "193") (pinfunction "DSI1_D2_N_193") (pintype "passive"))
    )
    (net (code "174") (name "Net-(rxPI1B-DSI1_D2_P)") (class "Default")
      (node (ref "H2") (pin "95") (pinfunction "95_95") (pintype "passive"))
      (node (ref "rxPI1") (pin "195") (pinfunction "DSI1_D2_P_195") (pintype "passive"))
    )
    (net (code "175") (name "Net-(rxPI1B-DSI1_D3_N)") (class "Default")
      (node (ref "H2") (pin "94") (pinfunction "94_94") (pintype "passive"))
      (node (ref "rxPI1") (pin "194") (pinfunction "DSI1_D3_N_194") (pintype "passive"))
    )
    (net (code "176") (name "Net-(rxPI1B-DSI1_D3_P)") (class "Default")
      (node (ref "H2") (pin "96") (pinfunction "96_96") (pintype "passive"))
      (node (ref "rxPI1") (pin "196") (pinfunction "DSI1_D3_P_196") (pintype "passive"))
    )
    (net (code "177") (name "Net-(rxPI1B-VDAC_COMP)") (class "Default")
      (node (ref "H2") (pin "11") (pinfunction "11_11") (pintype "passive"))
      (node (ref "rxPI1") (pin "111") (pinfunction "VDAC_COMP_111") (pintype "passive"))
    )
    (net (code "178") (name "Net-(rxPI1C-BT_HOST_WAKE)") (class "Default")
      (node (ref "J3") (pin "86") (pinfunction "86_86") (pintype "passive"))
      (node (ref "rxPI1") (pin "285") (pinfunction "BT_HOST_WAKE_285") (pintype "passive"))
    )
    (net (code "179") (name "Net-(rxPI1C-BT_REG_ON_H)") (class "Default")
      (node (ref "J3") (pin "97") (pinfunction "97_97") (pintype "passive"))
      (node (ref "rxPI1") (pin "298") (pinfunction "BT_REG_ON_H_298") (pintype "passive"))
    )
    (net (code "180") (name "Net-(rxPI1C-GPIO0_C2)") (class "Default")
      (node (ref "J3") (pin "94") (pinfunction "94_94") (pintype "passive"))
      (node (ref "rxPI1") (pin "293") (pinfunction "GPIO0_C2_293") (pintype "passive"))
    )
    (net (code "181") (name "Net-(rxPI1C-GPIO0_D3)") (class "Default")
      (node (ref "J3") (pin "93") (pinfunction "93_93") (pintype "passive"))
      (node (ref "rxPI1") (pin "294") (pinfunction "GPIO0_D3_294") (pintype "passive"))
    )
    (net (code "182") (name "Net-(rxPI1C-GPIO1_B6_CAM2_CLK)") (class "Default")
      (node (ref "J3") (pin "9") (pinfunction "9_9") (pintype "passive"))
      (node (ref "rxPI1") (pin "210") (pinfunction "GPIO1_B6_CAM2_CLK_210") (pintype "passive"))
    )
    (net (code "183") (name "Net-(rxPI1C-GPIO1_B7)") (class "Default")
      (node (ref "J3") (pin "11") (pinfunction "11_11") (pintype "passive"))
      (node (ref "rxPI1") (pin "212") (pinfunction "GPIO1_B7_212") (pintype "passive"))
    )
    (net (code "184") (name "Net-(rxPI1C-GPIO1_C1)") (class "Default")
      (node (ref "J3") (pin "19") (pinfunction "19_19") (pintype "passive"))
      (node (ref "rxPI1") (pin "220") (pinfunction "GPIO1_C1_220") (pintype "passive"))
    )
    (net (code "185") (name "Net-(rxPI1C-GPIO1_C4_S)") (class "Default")
      (node (ref "J3") (pin "80") (pinfunction "80_80") (pintype "passive"))
      (node (ref "rxPI1") (pin "279") (pinfunction "GPIO1_C4_S_279") (pintype "passive"))
    )
    (net (code "186") (name "Net-(rxPI1C-GPIO1_C6_S)") (class "Default")
      (node (ref "J3") (pin "76") (pinfunction "76_76") (pintype "passive"))
      (node (ref "rxPI1") (pin "275") (pinfunction "GPIO1_C6_S_275") (pintype "passive"))
    )
    (net (code "187") (name "Net-(rxPI1C-GPIO1_D0)") (class "Default")
      (node (ref "J3") (pin "43") (pinfunction "43_43") (pintype "passive"))
      (node (ref "rxPI1") (pin "244") (pinfunction "GPIO1_D0_244") (pintype "passive"))
    )
    (net (code "188") (name "Net-(rxPI1C-GPIO1_D1)") (class "Default")
      (node (ref "J3") (pin "45") (pinfunction "45_45") (pintype "passive"))
      (node (ref "rxPI1") (pin "246") (pinfunction "GPIO1_D1_246") (pintype "passive"))
    )
    (net (code "189") (name "Net-(rxPI1C-GPIO1_D2)") (class "Default")
      (node (ref "J3") (pin "84") (pinfunction "84_84") (pintype "passive"))
      (node (ref "rxPI1") (pin "283") (pinfunction "GPIO1_D2_283") (pintype "passive"))
    )
    (net (code "190") (name "Net-(rxPI1C-GPIO1_D5_S)") (class "Default")
      (node (ref "J3") (pin "78") (pinfunction "78_78") (pintype "passive"))
      (node (ref "rxPI1") (pin "277") (pinfunction "GPIO1_D5_S_277") (pintype "passive"))
    )
    (net (code "191") (name "Net-(rxPI1C-GPIO3_B7)") (class "Default")
      (node (ref "J3") (pin "5") (pinfunction "5_5") (pintype "passive"))
      (node (ref "rxPI1") (pin "206") (pinfunction "GPIO3_B7_206") (pintype "passive"))
    )
    (net (code "192") (name "Net-(rxPI1C-GPIO3_C0)") (class "Default")
      (node (ref "J3") (pin "3") (pinfunction "3_3") (pintype "passive"))
      (node (ref "rxPI1") (pin "204") (pinfunction "GPIO3_C0_204") (pintype "passive"))
    )
    (net (code "193") (name "Net-(rxPI1C-GPIO4_A4)") (class "Default")
      (node (ref "J3") (pin "37") (pinfunction "37_37") (pintype "passive"))
      (node (ref "rxPI1") (pin "238") (pinfunction "GPIO4_A4_238") (pintype "passive"))
    )
    (net (code "194") (name "Net-(rxPI1C-GPIO4_A5)") (class "Default")
      (node (ref "J3") (pin "39") (pinfunction "39_39") (pintype "passive"))
      (node (ref "rxPI1") (pin "240") (pinfunction "GPIO4_A5_240") (pintype "passive"))
    )
    (net (code "195") (name "Net-(rxPI1C-GPIO4_A6)") (class "Default")
      (node (ref "J3") (pin "90") (pinfunction "90_90") (pintype "passive"))
      (node (ref "rxPI1") (pin "289") (pinfunction "GPIO4_A6_289") (pintype "passive"))
    )
    (net (code "196") (name "Net-(rxPI1C-GPIO4_A7)") (class "Default")
      (node (ref "J3") (pin "88") (pinfunction "88_88") (pintype "passive"))
      (node (ref "rxPI1") (pin "287") (pinfunction "GPIO4_A7_287") (pintype "passive"))
    )
    (net (code "197") (name "Net-(rxPI1C-HP_DET_L)") (class "Default")
      (node (ref "J3") (pin "35") (pinfunction "35_35") (pintype "passive"))
      (node (ref "rxPI1") (pin "236") (pinfunction "HP_DET_L_236") (pintype "passive"))
    )
    (net (code "198") (name "Net-(rxPI1C-LCD_PWREN_H)") (class "Default")
      (node (ref "J3") (pin "33") (pinfunction "33_33") (pintype "passive"))
      (node (ref "rxPI1") (pin "234") (pinfunction "LCD_PWREN_H_234") (pintype "passive"))
    )
    (net (code "199") (name "Net-(rxPI1C-PCIE20_2_REFCLKN)") (class "Default")
      (node (ref "J3") (pin "42") (pinfunction "42_42") (pintype "passive"))
      (node (ref "rxPI1") (pin "241") (pinfunction "PCIE20_2_REFCLKN_241") (pintype "passive"))
    )
    (net (code "200") (name "Net-(rxPI1C-PCIE20_2_REFCLKP)") (class "Default")
      (node (ref "J3") (pin "40") (pinfunction "40_40") (pintype "passive"))
      (node (ref "rxPI1") (pin "239") (pinfunction "PCIE20_2_REFCLKP_239") (pintype "passive"))
    )
    (net (code "201") (name "Net-(rxPI1C-PWM11_M3)") (class "Default")
      (node (ref "J3") (pin "17") (pinfunction "17_17") (pintype "passive"))
      (node (ref "rxPI1") (pin "218") (pinfunction "PWM11_M3_218") (pintype "passive"))
    )
    (net (code "202") (name "Net-(rxPI1C-RTC_INT_L)") (class "Default")
      (node (ref "J3") (pin "82") (pinfunction "82_82") (pintype "passive"))
      (node (ref "rxPI1") (pin "281") (pinfunction "RTC_INT_L_281") (pintype "passive"))
    )
    (net (code "203") (name "Net-(rxPI1C-SARADC_VIN0_KEY{slash}RECOVERY)") (class "Default")
      (node (ref "J3") (pin "25") (pinfunction "25_25") (pintype "passive"))
      (node (ref "rxPI1") (pin "226") (pinfunction "SARADC_VIN0_KEY/RECOVERY_226") (pintype "passive"))
    )
    (net (code "204") (name "Net-(rxPI1C-SARADC_VIN1_DC)") (class "Default")
      (node (ref "J3") (pin "27") (pinfunction "27_27") (pintype "passive"))
      (node (ref "rxPI1") (pin "228") (pinfunction "SARADC_VIN1_DC_228") (pintype "passive"))
    )
    (net (code "205") (name "Net-(rxPI1C-SARADC_VIN2_HP_HOOK)") (class "Default")
      (node (ref "J3") (pin "29") (pinfunction "29_29") (pintype "passive"))
      (node (ref "rxPI1") (pin "230") (pinfunction "SARADC_VIN2_HP_HOOK_230") (pintype "passive"))
    )
    (net (code "206") (name "Net-(rxPI1C-SDMMC_DET_L)") (class "Default")
      (node (ref "J3") (pin "73") (pinfunction "73_73") (pintype "passive"))
      (node (ref "rxPI1") (pin "274") (pinfunction "SDMMC_DET_L_274") (pintype "passive"))
    )
    (net (code "207") (name "Net-(rxPI1C-TYPEC0_OTG_VBUSDET)") (class "Default")
      (node (ref "J3") (pin "98") (pinfunction "98_98") (pintype "passive"))
      (node (ref "rxPI1") (pin "297") (pinfunction "TYPEC0_OTG_VBUSDET_297") (pintype "passive"))
    )
    (net (code "208") (name "Net-(rxPI1C-TYPEC0_SBU1)") (class "Default")
      (node (ref "J3") (pin "4") (pinfunction "4_4") (pintype "passive"))
      (node (ref "rxPI1") (pin "203") (pinfunction "TYPEC0_SBU1_203") (pintype "passive"))
    )
    (net (code "209") (name "Net-(rxPI1C-TYPEC0_SBU1_DC)") (class "Default")
      (node (ref "J3") (pin "7") (pinfunction "7_7") (pintype "passive"))
      (node (ref "rxPI1") (pin "208") (pinfunction "TYPEC0_SBU1_DC_208") (pintype "passive"))
    )
    (net (code "210") (name "Net-(rxPI1C-TYPEC0_SBU2)") (class "Default")
      (node (ref "J3") (pin "6") (pinfunction "6_6") (pintype "passive"))
      (node (ref "rxPI1") (pin "205") (pinfunction "TYPEC0_SBU2_205") (pintype "passive"))
    )
    (net (code "211") (name "Net-(rxPI1C-TYPEC0_SBU2_DC)") (class "Default")
      (node (ref "J3") (pin "13") (pinfunction "13_13") (pintype "passive"))
      (node (ref "rxPI1") (pin "214") (pinfunction "TYPEC0_SBU2_DC_214") (pintype "passive"))
    )
    (net (code "212") (name "Net-(rxPI1C-TYPEC0_SSRX2N)") (class "Default")
      (node (ref "J3") (pin "24") (pinfunction "24_24") (pintype "passive"))
      (node (ref "rxPI1") (pin "223") (pinfunction "TYPEC0_SSRX2N_223") (pintype "passive"))
    )
    (net (code "213") (name "Net-(rxPI1C-TYPEC0_SSRX2P)") (class "Default")
      (node (ref "J3") (pin "22") (pinfunction "22_22") (pintype "passive"))
      (node (ref "rxPI1") (pin "221") (pinfunction "TYPEC0_SSRX2P_221") (pintype "passive"))
    )
    (net (code "214") (name "Net-(rxPI1C-TYPEC0_SSTX2N)") (class "Default")
      (node (ref "J3") (pin "30") (pinfunction "30_30") (pintype "passive"))
      (node (ref "rxPI1") (pin "229") (pinfunction "TYPEC0_SSTX2N_229") (pintype "passive"))
    )
    (net (code "215") (name "Net-(rxPI1C-TYPEC0_SSTX2P)") (class "Default")
      (node (ref "J3") (pin "28") (pinfunction "28_28") (pintype "passive"))
      (node (ref "rxPI1") (pin "227") (pinfunction "TYPEC0_SSTX2P_227") (pintype "passive"))
    )
    (net (code "216") (name "Net-(rxPI1C-TYPEC5V_PWREN_H)") (class "Default")
      (node (ref "J3") (pin "96") (pinfunction "96_96") (pintype "passive"))
      (node (ref "rxPI1") (pin "295") (pinfunction "TYPEC5V_PWREN_H_295") (pintype "passive"))
    )
    (net (code "217") (name "Net-(rxPI1C-VCC_SD_3V3_S3)") (class "Default")
      (node (ref "J3") (pin "91") (pinfunction "91_91") (pintype "passive"))
      (node (ref "R3") (pin "2") (pinfunction "2_2") (pintype "passive"))
      (node (ref "rxPI1") (pin "292") (pinfunction "VCC_SD_3V3_S3_292") (pintype "passive"))
    )
    (net (code "218") (name "Net-(rxPI1C-WIFI_PWR_EN)") (class "Default")
      (node (ref "J3") (pin "23") (pinfunction "23_23") (pintype "passive"))
      (node (ref "rxPI1") (pin "224") (pinfunction "WIFI_PWR_EN_224") (pintype "passive"))
    )
    (net (code "219") (name "PCIe_CLK_N") (class "Default")
      (node (ref "H2") (pin "12") (pinfunction "12_12") (pintype "passive"))
      (node (ref "HB") (pin "11") (pinfunction "11_11") (pintype "passive"))
      (node (ref "rPI1") (pin "112") (pinfunction "PCIe_CLK_N_112") (pintype "passive"))
      (node (ref "rxPI1") (pin "112") (pinfunction "PCIe_CLK_N_112") (pintype "passive"))
    )
    (net (code "220") (name "PCIe_CLK_P") (class "Default")
      (node (ref "H2") (pin "10") (pinfunction "10_10") (pintype "passive"))
      (node (ref "HB") (pin "9") (pinfunction "9_9") (pintype "passive"))
      (node (ref "rPI1") (pin "110") (pinfunction "PCIe_CLK_P_110") (pintype "passive"))
      (node (ref "rxPI1") (pin "110") (pinfunction "PCIe_CLK_P_110") (pintype "passive"))
    )
    (net (code "221") (name "PCIe_CLK_nREQ") (class "Default")
      (node (ref "H2") (pin "2") (pinfunction "2_2") (pintype "passive"))
      (node (ref "HB") (pin "1") (pinfunction "1_1") (pintype "passive"))
      (node (ref "rPI1") (pin "102") (pinfunction "PCIe_CLK_nREQ_102") (pintype "passive"))
      (node (ref "rxPI1") (pin "102") (pinfunction "PCIe_CLK_nREQ_102") (pintype "passive"))
    )
    (net (code "222") (name "PCIe_RX_N") (class "Default")
      (node (ref "H2") (pin "18") (pinfunction "18_18") (pintype "passive"))
      (node (ref "HB") (pin "17") (pinfunction "17_17") (pintype "passive"))
      (node (ref "rPI1") (pin "118") (pinfunction "PCIe_RX_N_118") (pintype "passive"))
      (node (ref "rxPI1") (pin "118") (pinfunction "PCIe_RX_N_118") (pintype "passive"))
    )
    (net (code "223") (name "PCIe_RX_P") (class "Default")
      (node (ref "H2") (pin "16") (pinfunction "16_16") (pintype "passive"))
      (node (ref "HB") (pin "15") (pinfunction "15_15") (pintype "passive"))
      (node (ref "rPI1") (pin "116") (pinfunction "PCIe_RX_P_116") (pintype "passive"))
      (node (ref "rxPI1") (pin "116") (pinfunction "PCIe_RX_P_116") (pintype "passive"))
    )
    (net (code "224") (name "PCIe_TX_N") (class "Default")
      (node (ref "H2") (pin "24") (pinfunction "24_24") (pintype "passive"))
      (node (ref "HB") (pin "23") (pinfunction "23_23") (pintype "passive"))
      (node (ref "rPI1") (pin "124") (pinfunction "PCIe_TX_N_124") (pintype "passive"))
      (node (ref "rxPI1") (pin "124") (pinfunction "PCIe_TX_N_124") (pintype "passive"))
    )
    (net (code "225") (name "PCIe_TX_P") (class "Default")
      (node (ref "H2") (pin "22") (pinfunction "22_22") (pintype "passive"))
      (node (ref "HB") (pin "21") (pinfunction "21_21") (pintype "passive"))
      (node (ref "rPI1") (pin "122") (pinfunction "PCIe_TX_P_122") (pintype "passive"))
      (node (ref "rxPI1") (pin "122") (pinfunction "PCIe_TX_P_122") (pintype "passive"))
    )
    (net (code "226") (name "PCIe_nRST") (class "Default")
      (node (ref "H2") (pin "9") (pinfunction "9_9") (pintype "passive"))
      (node (ref "HB") (pin "10") (pinfunction "10_10") (pintype "passive"))
      (node (ref "rPI1") (pin "109") (pinfunction "PCIe_nRST_109") (pintype "passive"))
      (node (ref "rxPI1") (pin "109") (pinfunction "PCIe_nRST_109") (pintype "passive"))
    )
    (net (code "227") (name "PRG_CC1") (class "Default")
      (node (ref "J1") (pin "A5") (pinfunction "CC1_A5") (pintype "bidirectional"))
      (node (ref "R1") (pin "1") (pinfunction "1_1") (pintype "passive"))
      (node (ref "U1") (pin "10") (pinfunction "CC1_10") (pintype "bidirectional"))
      (node (ref "U1") (pin "11") (pinfunction "CC1_11") (pintype "bidirectional"))
    )
    (net (code "228") (name "PRG_CC2") (class "Default")
      (node (ref "J1") (pin "B5") (pinfunction "CC2_B5") (pintype "bidirectional"))
      (node (ref "U1") (pin "1") (pinfunction "CC2_1") (pintype "bidirectional"))
      (node (ref "U1") (pin "14") (pinfunction "CC2_14") (pintype "bidirectional"))
    )
    (net (code "229") (name "RD_CC1") (class "Default")
      (node (ref "HB") (pin "98") (pinfunction "98_98") (pintype "passive"))
      (node (ref "R1") (pin "2") (pinfunction "2_2") (pintype "passive"))
      (node (ref "rPI1") (pin "197") (pinfunction "GND_197") (pintype "passive"))
    )
    (net (code "230") (name "Res104") (class "Default")
      (node (ref "H2") (pin "4") (pinfunction "4_4") (pintype "passive"))
      (node (ref "HB") (pin "3") (pinfunction "3_3") (pintype "passive"))
      (node (ref "rPI1") (pin "104") (pinfunction "PCIE_nWAKE_104") (pintype "passive"))
      (node (ref "rxPI1") (pin "104") (pinfunction "Reserved_104") (pintype "passive"))
    )
    (net (code "231") (name "Res106") (class "Default")
      (node (ref "H2") (pin "6") (pinfunction "6_6") (pintype "passive"))
      (node (ref "HB") (pin "5") (pinfunction "5_5") (pintype "passive"))
      (node (ref "rPI1") (pin "106") (pinfunction "PCIE_PWR_EN_106") (pintype "passive"))
      (node (ref "rxPI1") (pin "106") (pinfunction "Reserved_106") (pintype "passive"))
    )
    (net (code "232") (name "USB20_N") (class "Default")
      (node (ref "HB") (pin "4") (pinfunction "4_4") (pintype "passive"))
      (node (ref "J3") (pin "66") (pinfunction "66_66") (pintype "passive"))
      (node (ref "rPI1") (pin "103") (pinfunction "USB2_N_103") (pintype "passive"))
      (node (ref "rxPI1") (pin "265") (pinfunction "USB20_HOST0_DM_265") (pintype "passive"))
    )
    (net (code "233") (name "USB20_P") (class "Default")
      (node (ref "HB") (pin "6") (pinfunction "6_6") (pintype "passive"))
      (node (ref "J3") (pin "64") (pinfunction "64_64") (pintype "passive"))
      (node (ref "rPI1") (pin "105") (pinfunction "USB2_P_105") (pintype "passive"))
      (node (ref "rxPI1") (pin "263") (pinfunction "USB20_HOST0_DP_263") (pintype "passive"))
    )
    (net (code "234") (name "USB30_RX1_N") (class "Default")
      (node (ref "HB") (pin "27") (pinfunction "27_27") (pintype "passive"))
      (node (ref "J3") (pin "12") (pinfunction "12_12") (pintype "passive"))
      (node (ref "rPI1") (pin "128") (pinfunction "USB3-0-RX_N_128") (pintype "passive"))
      (node (ref "rxPI1") (pin "211") (pinfunction "TYPEC0_SSRX1N_211") (pintype "passive"))
    )
    (net (code "235") (name "USB30_RX1_P") (class "Default")
      (node (ref "HB") (pin "29") (pinfunction "29_29") (pintype "passive"))
      (node (ref "J3") (pin "10") (pinfunction "10_10") (pintype "passive"))
      (node (ref "rPI1") (pin "130") (pinfunction "USB3-0-RX_P_130") (pintype "passive"))
      (node (ref "rxPI1") (pin "209") (pinfunction "TYPEC0_SSRX1P_209") (pintype "passive"))
    )
    (net (code "236") (name "USB30_TX1_N") (class "Default")
      (node (ref "HB") (pin "39") (pinfunction "39_39") (pintype "passive"))
      (node (ref "J3") (pin "18") (pinfunction "18_18") (pintype "passive"))
      (node (ref "rPI1") (pin "140") (pinfunction "USB3-0-TX_N_140") (pintype "passive"))
      (node (ref "rxPI1") (pin "217") (pinfunction "TYPEC0_SSTX1N_217") (pintype "passive"))
    )
    (net (code "237") (name "USB30_TX1_P") (class "Default")
      (node (ref "HB") (pin "41") (pinfunction "41_41") (pintype "passive"))
      (node (ref "J3") (pin "16") (pinfunction "16_16") (pintype "passive"))
      (node (ref "rPI1") (pin "142") (pinfunction "USB3-0-TX_P_142") (pintype "passive"))
      (node (ref "rxPI1") (pin "215") (pinfunction "TYPEC0_SSTX1P_215") (pintype "passive"))
    )
    (net (code "238") (name "USB31_D_N") (class "Default")
      (node (ref "HB") (pin "66") (pinfunction "66_66") (pintype "passive"))
      (node (ref "J3") (pin "48") (pinfunction "48_48") (pintype "passive"))
      (node (ref "rPI1") (pin "165") (pinfunction "USB3-1-D_N_165") (pintype "passive"))
      (node (ref "rxPI1") (pin "247") (pinfunction "USB20_HOST1_DM_247") (pintype "passive"))
    )
    (net (code "239") (name "USB31_D_P") (class "Default")
      (node (ref "HB") (pin "64") (pinfunction "64_64") (pintype "passive"))
      (node (ref "J3") (pin "46") (pinfunction "46_46") (pintype "passive"))
      (node (ref "rPI1") (pin "163") (pinfunction "USB3-1-D_P_163") (pintype "passive"))
      (node (ref "rxPI1") (pin "245") (pinfunction "USB20_HOST1_DP_245") (pintype "passive"))
    )
    (net (code "240") (name "USB31_RX_N") (class "Default")
      (node (ref "HB") (pin "58") (pinfunction "58_58") (pintype "passive"))
      (node (ref "J3") (pin "60") (pinfunction "60_60") (pintype "passive"))
      (node (ref "rPI1") (pin "157") (pinfunction "USB3-1-RX_N_157") (pintype "passive"))
      (node (ref "rxPI1") (pin "259") (pinfunction "C42_-_RXN_259") (pintype "passive"))
    )
    (net (code "241") (name "USB31_RX_P") (class "Default")
      (node (ref "HB") (pin "60") (pinfunction "60_60") (pintype "passive"))
      (node (ref "J3") (pin "58") (pinfunction "58_58") (pintype "passive"))
      (node (ref "rPI1") (pin "159") (pinfunction "USB3-1-RX_P_159") (pintype "passive"))
      (node (ref "rxPI1") (pin "257") (pinfunction "D42_-_RXP_257") (pintype "passive"))
    )
    (net (code "242") (name "USB31_TX_N") (class "Default")
      (node (ref "HB") (pin "70") (pinfunction "70_70") (pintype "passive"))
      (node (ref "J3") (pin "54") (pinfunction "54_54") (pintype "passive"))
      (node (ref "rPI1") (pin "169") (pinfunction "USB3-1-TX_N_169") (pintype "passive"))
      (node (ref "rxPI1") (pin "253") (pinfunction "D41_-_TXN_253") (pintype "passive"))
    )
    (net (code "243") (name "USB31_TX_P") (class "Default")
      (node (ref "HB") (pin "72") (pinfunction "72_72") (pintype "passive"))
      (node (ref "J3") (pin "52") (pinfunction "52_52") (pintype "passive"))
      (node (ref "rPI1") (pin "171") (pinfunction "USB3-1-TX_P_171") (pintype "passive"))
      (node (ref "rxPI1") (pin "251") (pinfunction "E41_-_TXP_251") (pintype "passive"))
    )
    (net (code "244") (name "USBP_D_N") (class "Default")
      (node (ref "D1") (pin "6") (pinfunction "I/O1_6") (pintype "bidirectional"))
      (node (ref "J1") (pin "A7") (pinfunction "DN1_A7") (pintype "bidirectional"))
      (node (ref "J1") (pin "B7") (pinfunction "DN2_B7") (pintype "bidirectional"))
    )
    (net (code "245") (name "USBP_D_P") (class "Default")
      (node (ref "D1") (pin "4") (pinfunction "I/O2_4") (pintype "bidirectional"))
      (node (ref "J1") (pin "A6") (pinfunction "DP1_A6") (pintype "bidirectional"))
      (node (ref "J1") (pin "B6") (pinfunction "DP2_B6") (pintype "bidirectional"))
    )
    (net (code "246") (name "USB_OTG_D_N") (class "Default")
      (node (ref "H2") (pin "3") (pinfunction "3_3") (pintype "passive"))
      (node (ref "HB") (pin "35") (pinfunction "35_35") (pintype "passive"))
      (node (ref "L1") (pin "1") (pinfunction "1_1") (pintype "passive"))
      (node (ref "rPI1") (pin "136") (pinfunction "USB3-0-D_N_136") (pintype "passive"))
      (node (ref "rxPI1") (pin "103") (pinfunction "USB2_N_103") (pintype "passive"))
    )
    (net (code "247") (name "USB_OTG_D_P") (class "Default")
      (node (ref "H2") (pin "5") (pinfunction "5_5") (pintype "passive"))
      (node (ref "HB") (pin "33") (pinfunction "33_33") (pintype "passive"))
      (node (ref "L1") (pin "2") (pinfunction "2_2") (pintype "passive"))
      (node (ref "rPI1") (pin "134") (pinfunction "USB3-0-D_P_134") (pintype "passive"))
      (node (ref "rxPI1") (pin "105") (pinfunction "USB2_P_105") (pintype "passive"))
    )
    (net (code "248") (name "USB_OTG_ID") (class "Default")
      (node (ref "H2") (pin "1") (pinfunction "1_1") (pintype "passive"))
      (node (ref "HB") (pin "2") (pinfunction "2_2") (pintype "passive"))
      (node (ref "rPI1") (pin "101") (pinfunction "USB_OTG_ID_101") (pintype "passive"))
      (node (ref "rxPI1") (pin "101") (pinfunction "USB_OTG_ID_101") (pintype "passive"))
    )
    (net (code "249") (name "VCC_3V3_S3") (class "Default")
      (node (ref "H1") (pin "84") (pinfunction "84_84") (pintype "passive"))
      (node (ref "HA") (pin "83") (pinfunction "83_83") (pintype "passive"))
      (node (ref "R2") (pin "2") (pinfunction "2_2") (pintype "passive"))
      (node (ref "R3") (pin "1") (pinfunction "1_1") (pintype "passive"))
      (node (ref "U1") (pin "3") (pinfunction "VDD_3") (pintype "power_in"))
      (node (ref "U1") (pin "4") (pinfunction "VDD_4") (pintype "power_in"))
      (node (ref "rPI1") (pin "84") (pinfunction "+3.3v_(Output)_84") (pintype "passive"))
      (node (ref "rxPI1") (pin "84") (pinfunction "+3.3v_(Output)_84") (pintype "passive"))
    )
    (net (code "250") (name "unconnected-(J1-SBU1-PadA8)") (class "Default")
      (node (ref "J1") (pin "A8") (pinfunction "SBU1_A8") (pintype "bidirectional"))
    )
    (net (code "251") (name "unconnected-(J1-SBU2-PadB8)") (class "Default")
      (node (ref "J1") (pin "B8") (pinfunction "SBU2_B8") (pintype "bidirectional"))
    )
  )
)
